# EEZ_DIB_DCM220_r2B4.net
KiCad netlist of a schematic drawn in EAGLE
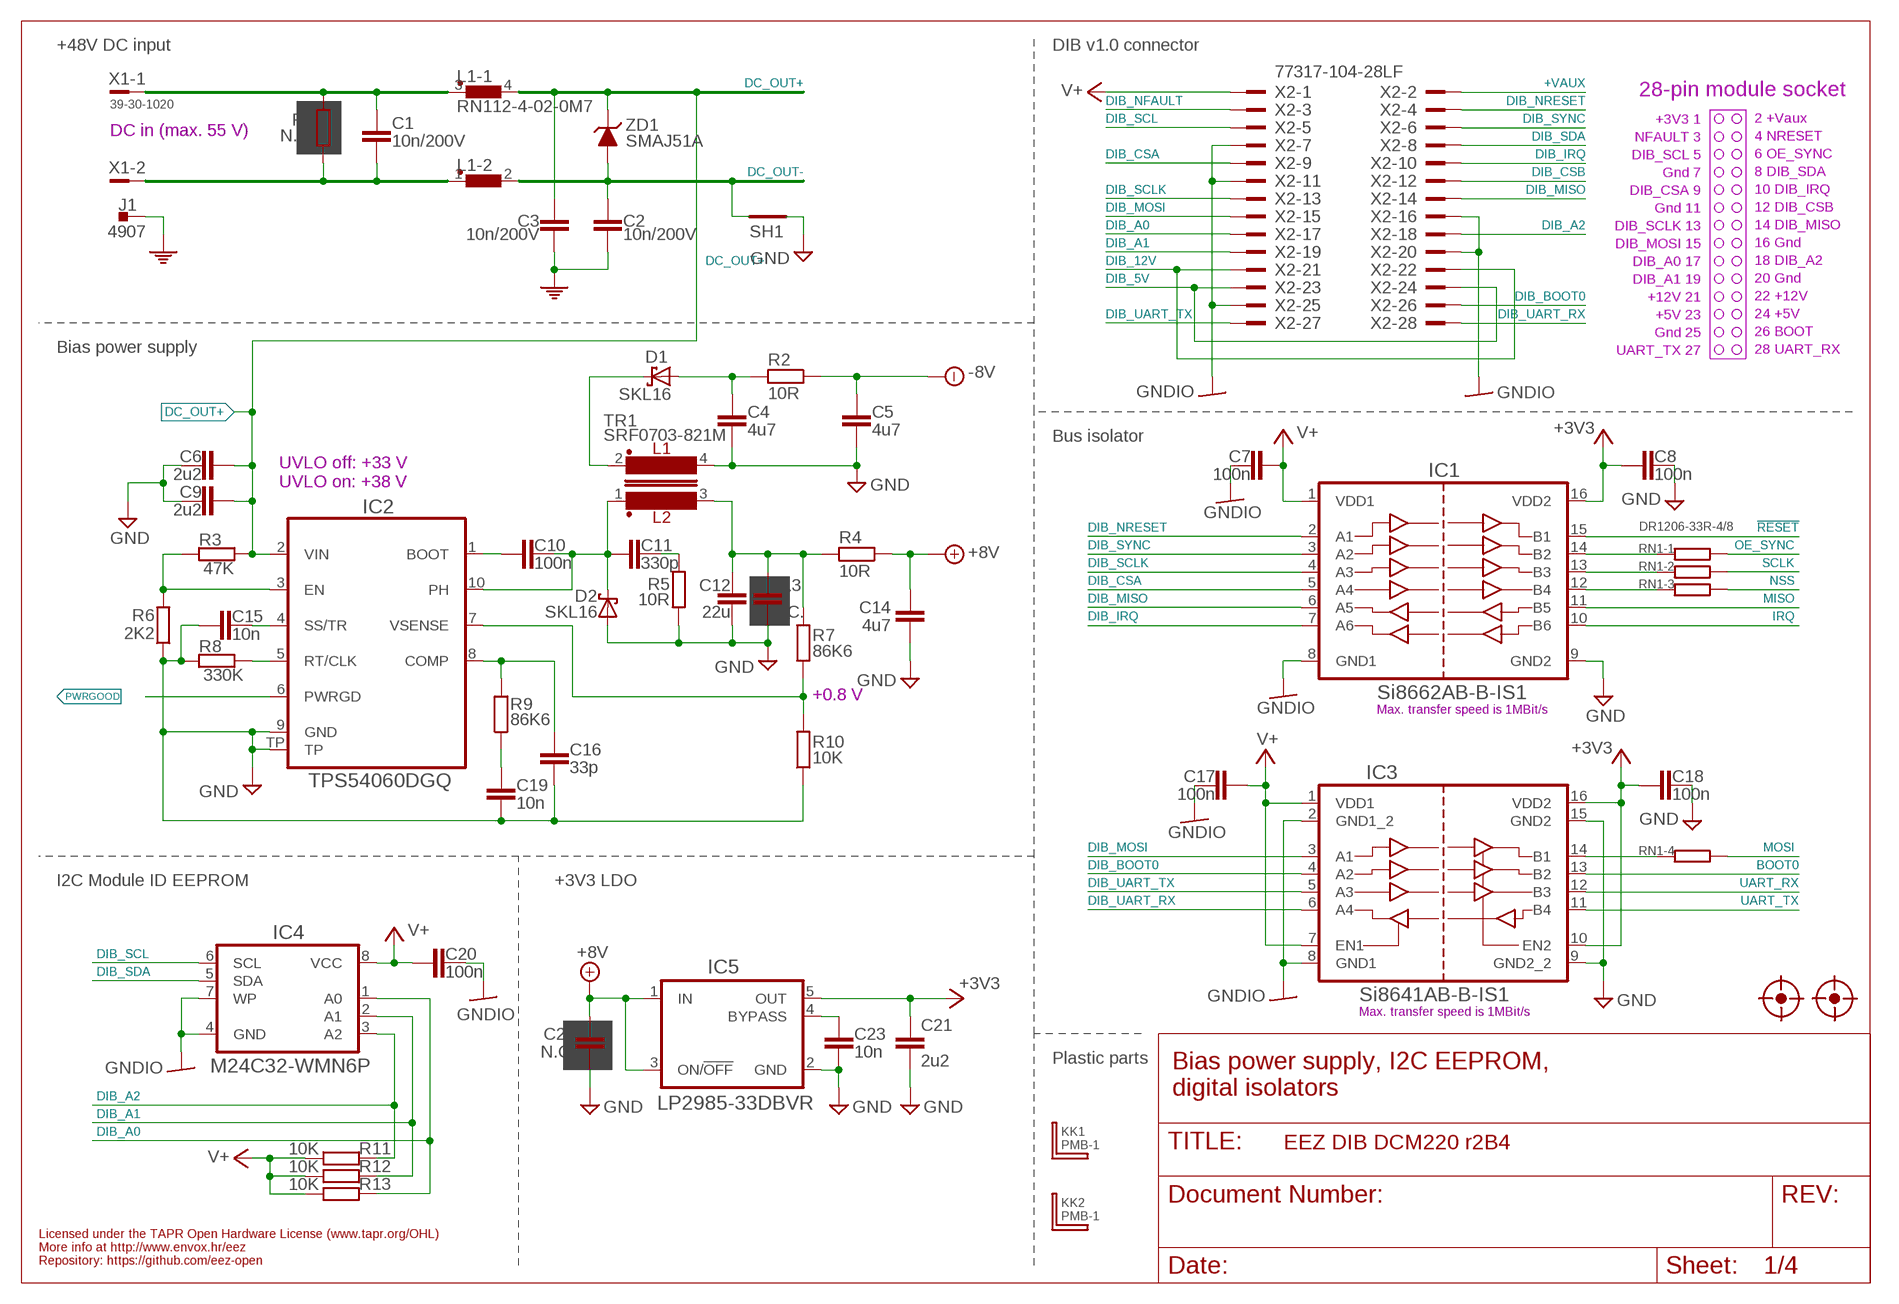
[diagram p0: schematic, sheet 1]
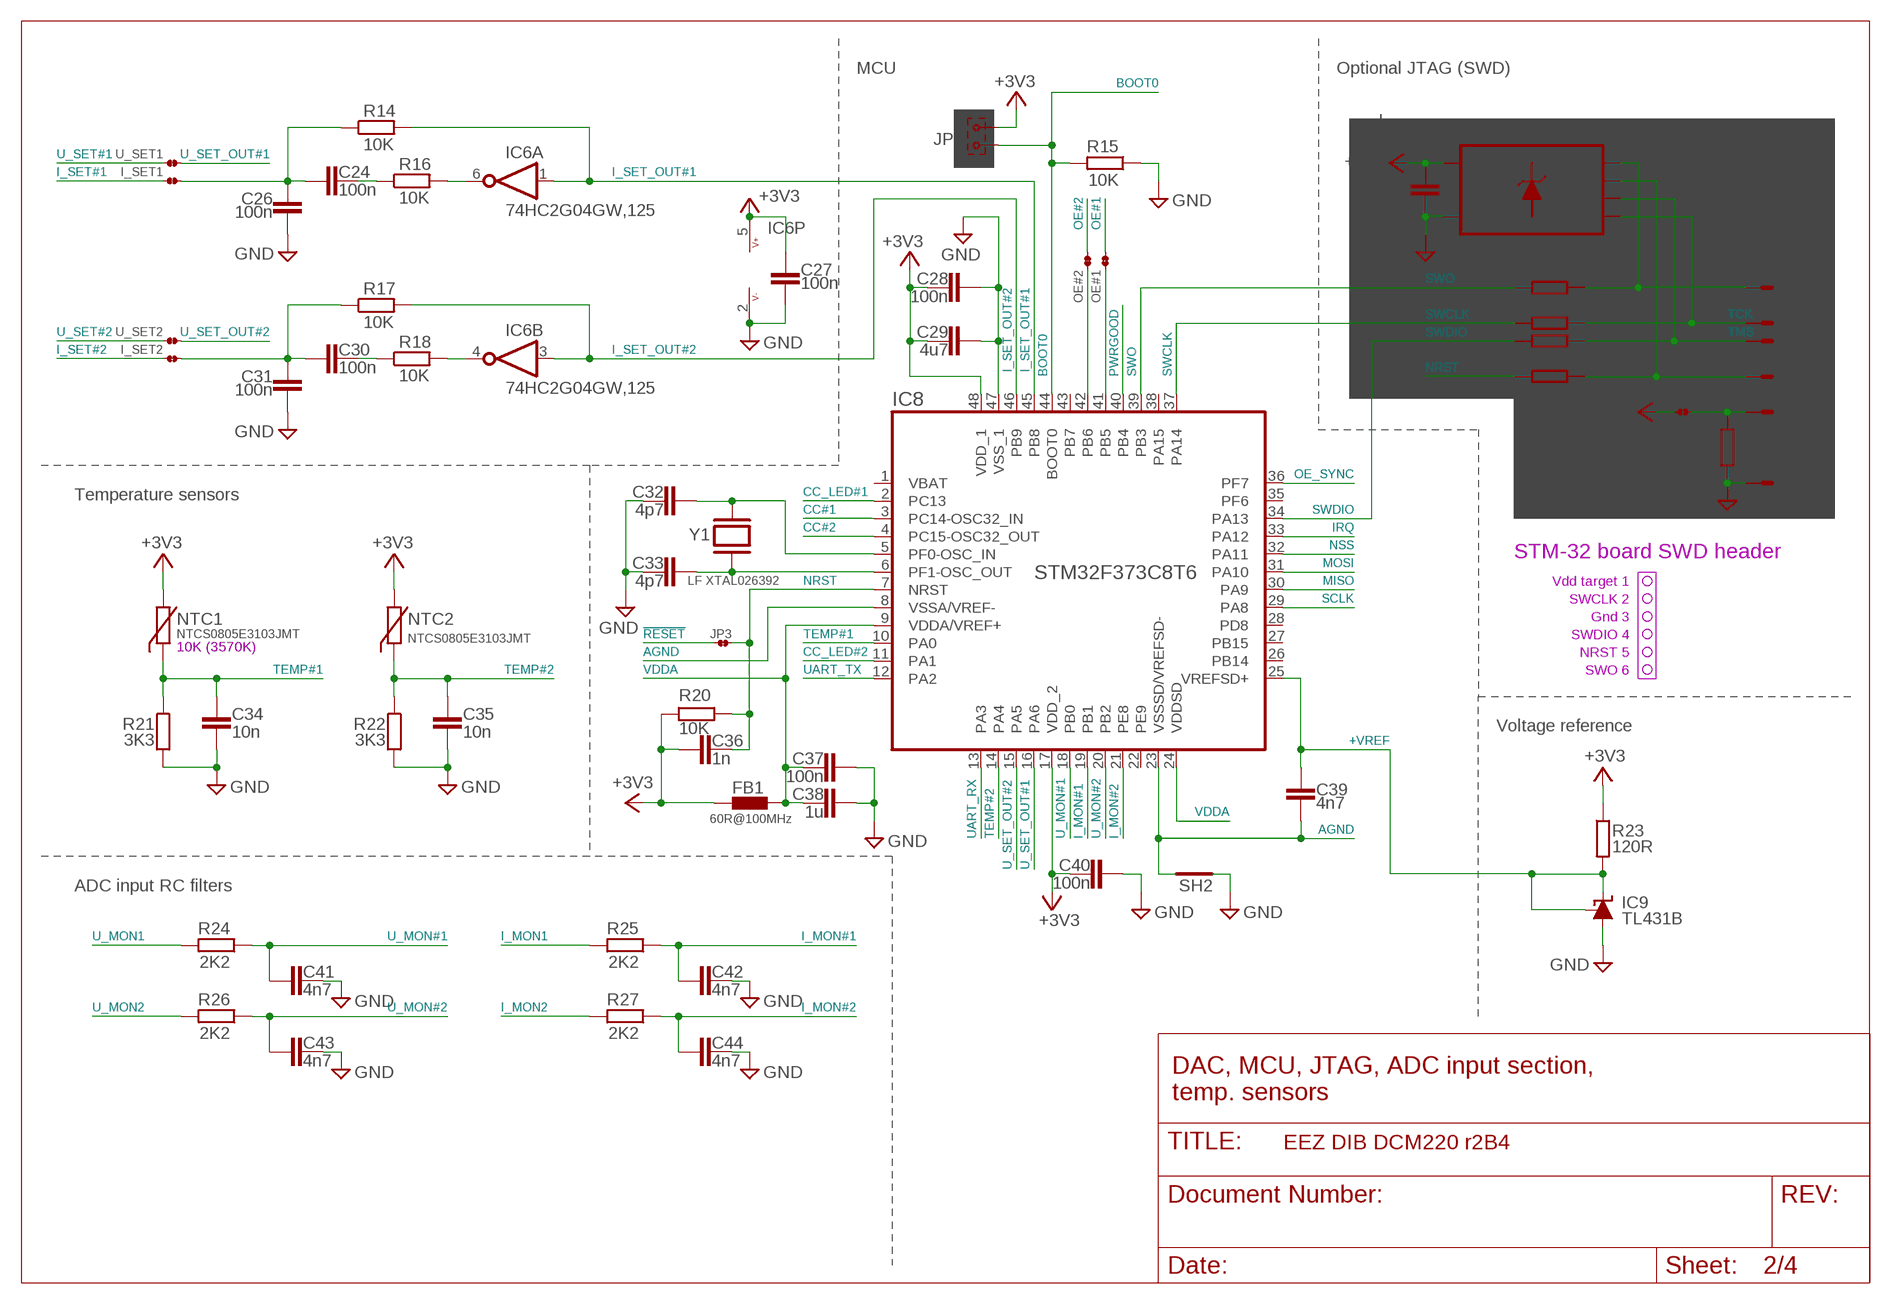
[diagram p1: schematic, sheet 2]
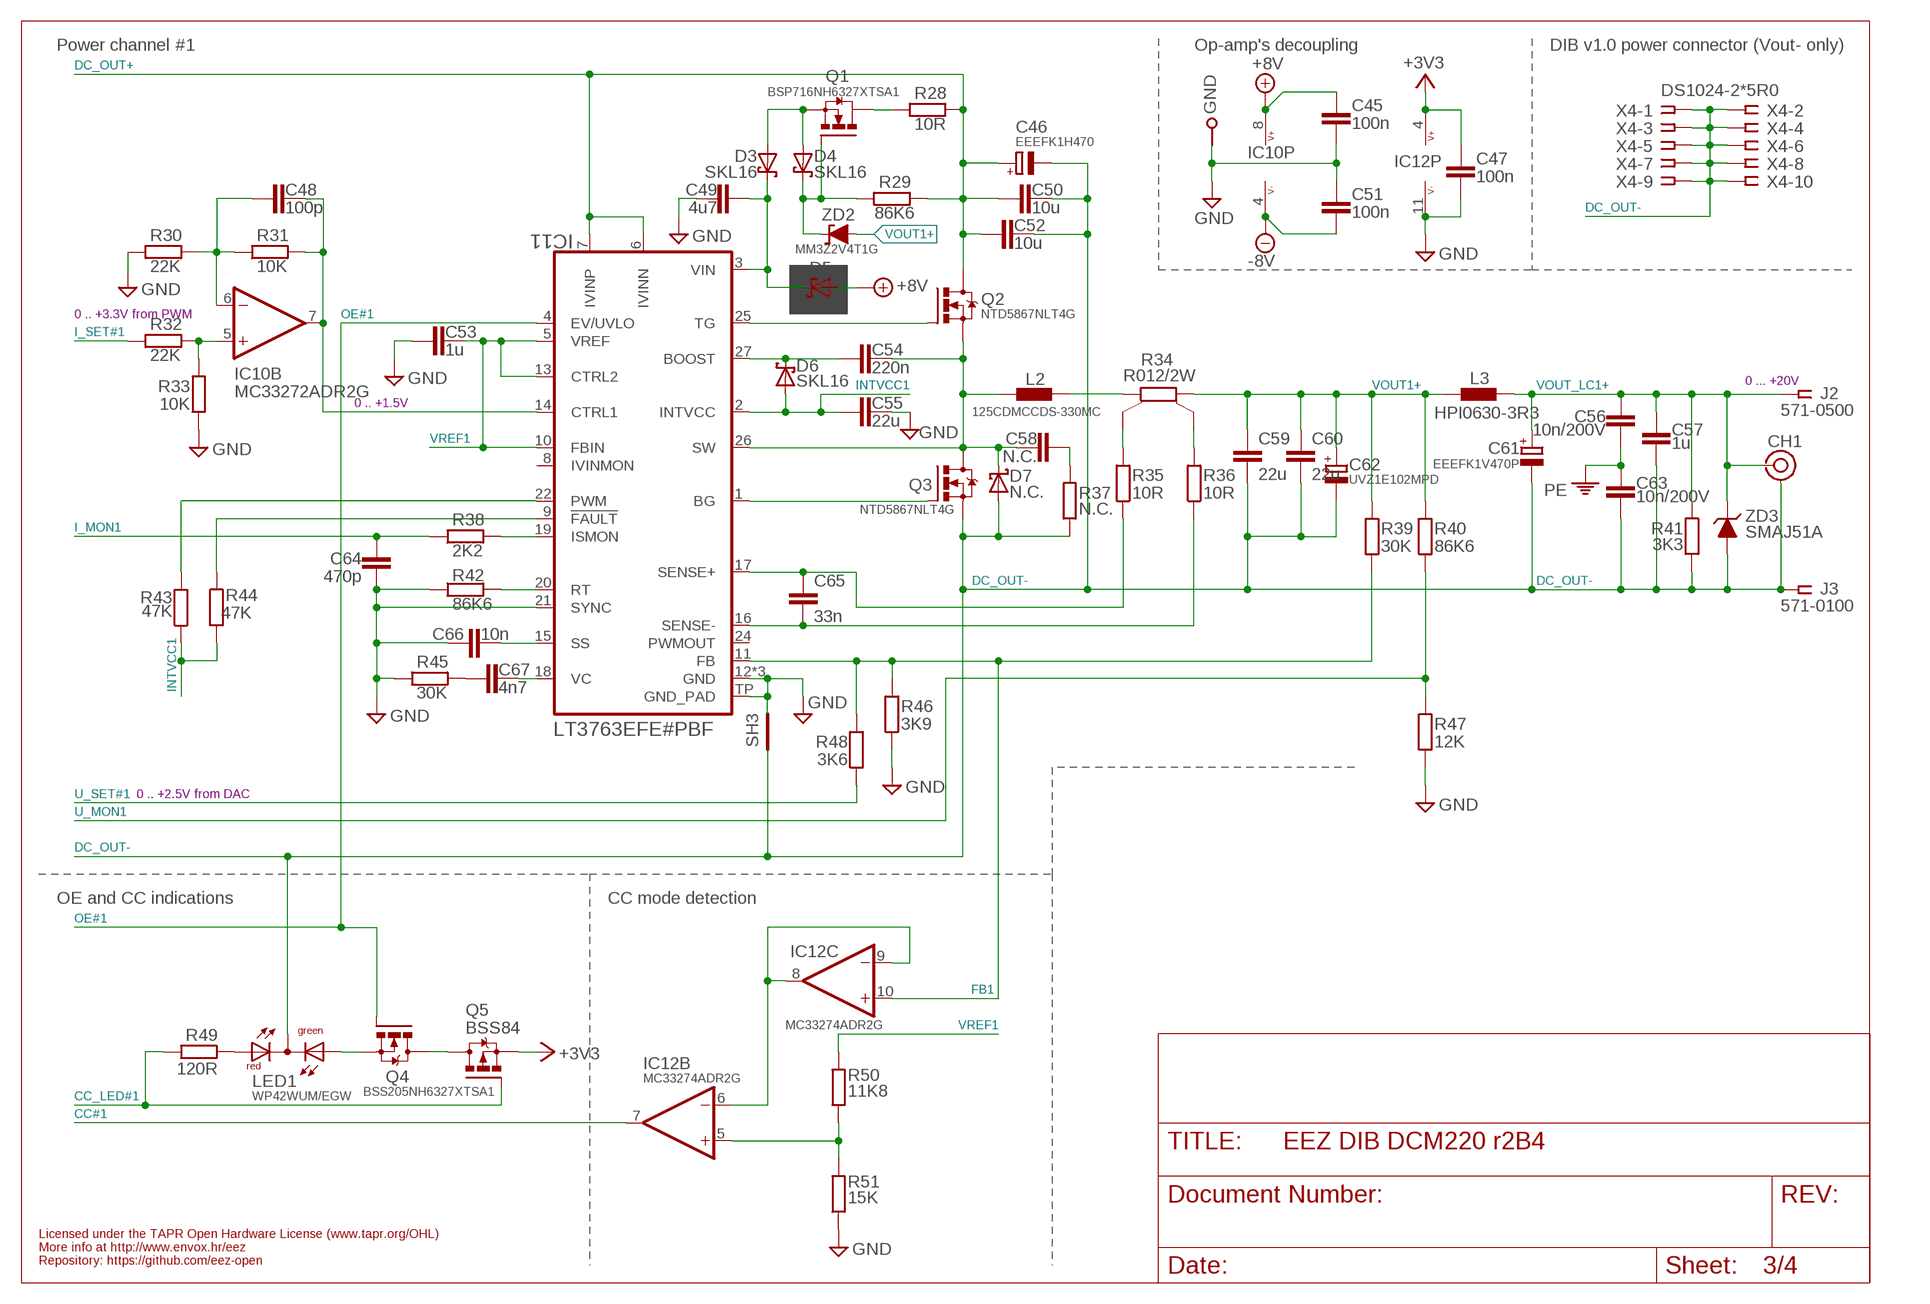
[diagram p2: schematic, sheet 3]
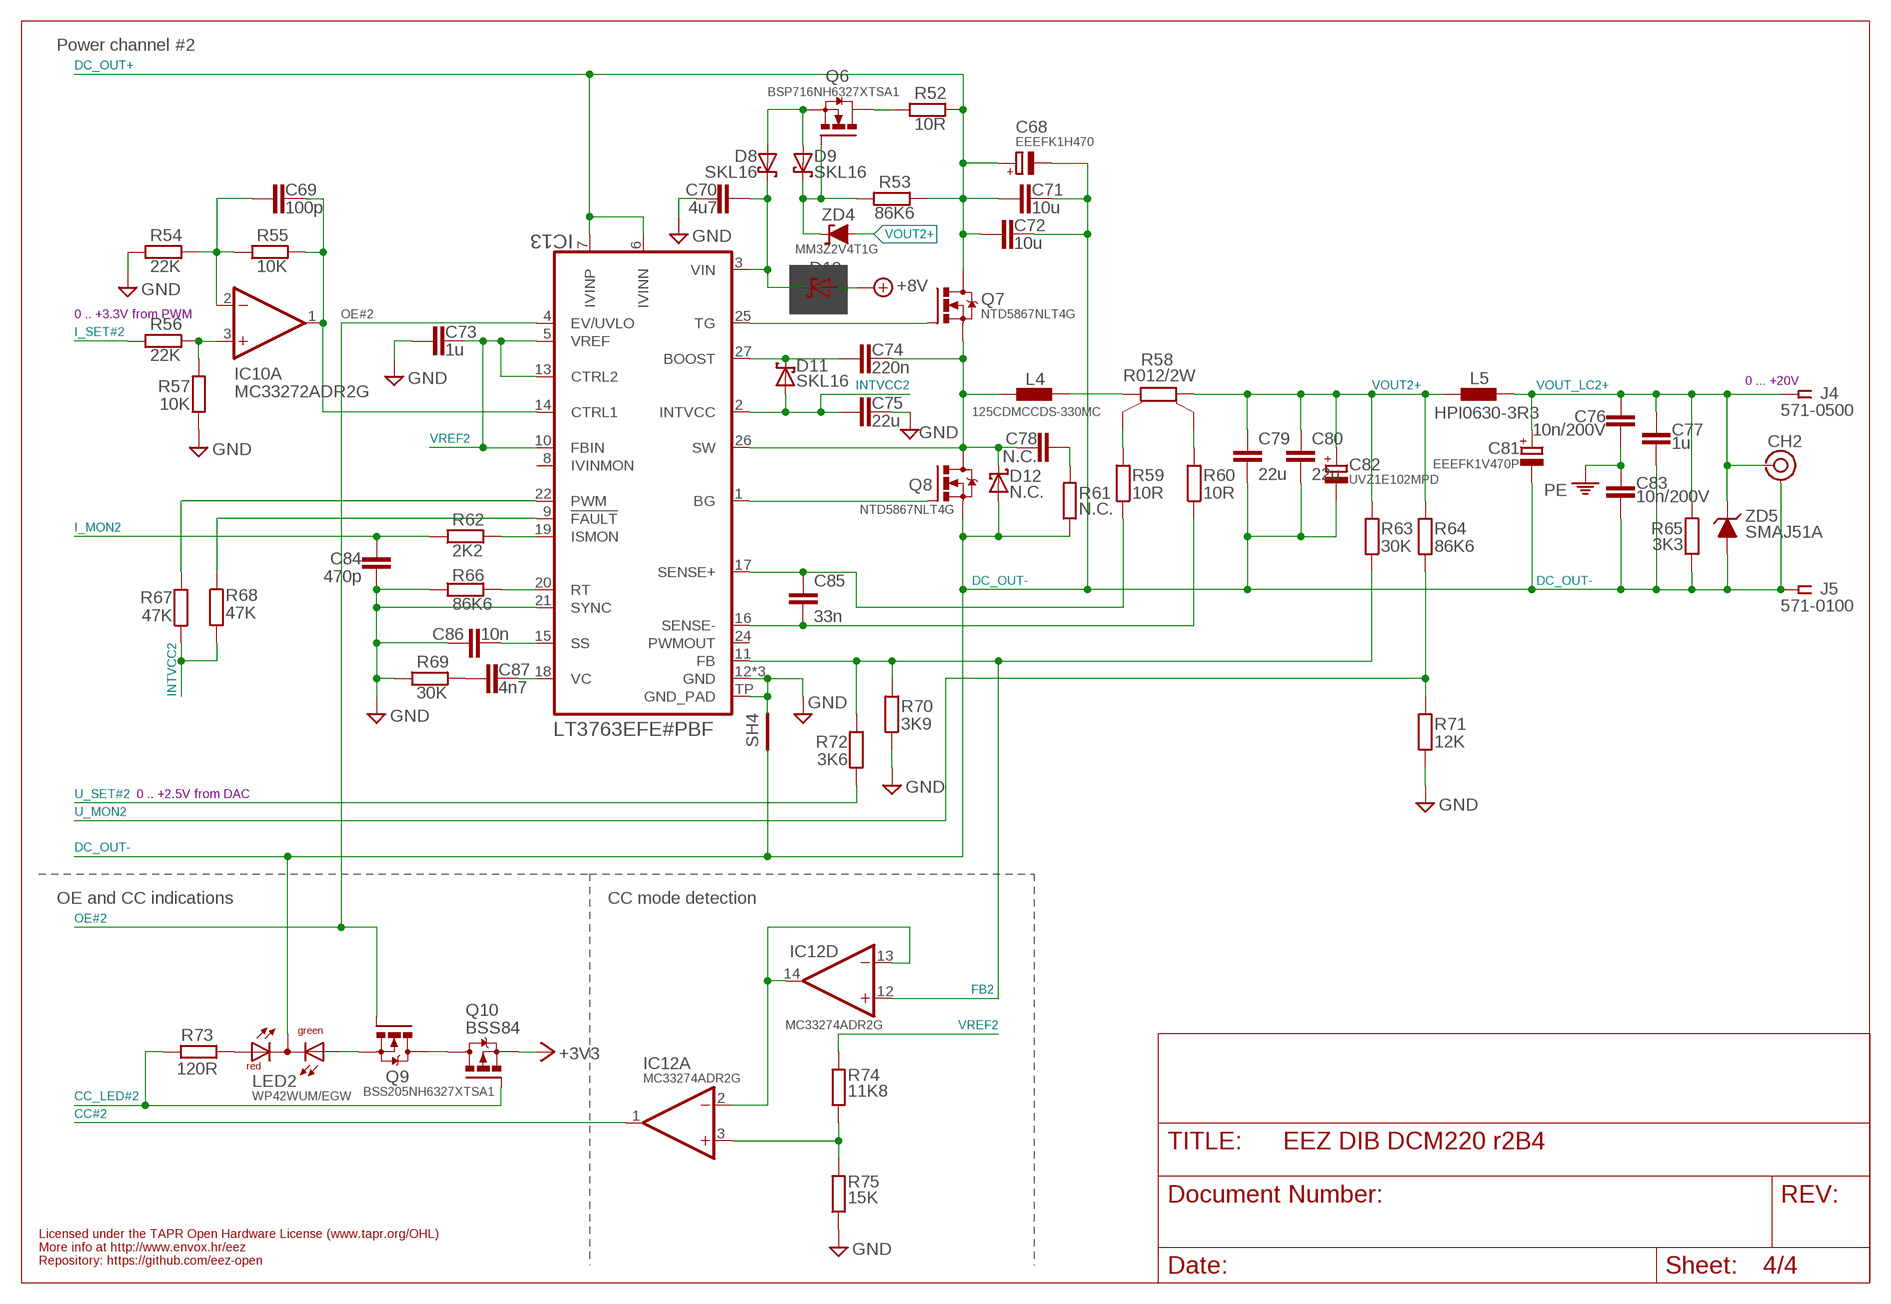
[diagram p3: schematic, sheet 4]

(export (version "E")
  (design (tool "Eeschema 10.0.6"))
  (components
    (comp (ref "C1")
      (value "10n/200V")
      (footprint "eagle-import:C1206")
      (libsource (lib "eagle-import") (part "C-EUC1206"))
    )
    (comp (ref "C2")
      (value "10n/200V")
      (footprint "eagle-import:C1206")
      (libsource (lib "eagle-import") (part "C-EUC1206"))
    )
    (comp (ref "C3")
      (value "10n/200V")
      (footprint "eagle-import:C1206")
      (libsource (lib "eagle-import") (part "C-EUC1206"))
    )
    (comp (ref "C4")
      (value "4u7")
      (footprint "eagle-import:C1206")
      (libsource (lib "eagle-import") (part "C-EUC1206"))
    )
    (comp (ref "C5")
      (value "4u7")
      (footprint "eagle-import:C1206")
      (libsource (lib "eagle-import") (part "C-EUC1206"))
    )
    (comp (ref "C6")
      (value "2u2")
      (footprint "eagle-import:C1206")
      (libsource (lib "eagle-import") (part "C-EUC1206"))
    )
    (comp (ref "C7")
      (value "100n")
      (footprint "eagle-import:C0603")
      (libsource (lib "eagle-import") (part "C-EUC0603"))
    )
    (comp (ref "C8")
      (value "100n")
      (footprint "eagle-import:C0603")
      (libsource (lib "eagle-import") (part "C-EUC0603"))
    )
    (comp (ref "C9")
      (value "2u2")
      (footprint "eagle-import:C1206")
      (libsource (lib "eagle-import") (part "C-EUC1206"))
    )
    (comp (ref "C10")
      (value "100n")
      (footprint "eagle-import:C0603")
      (libsource (lib "eagle-import") (part "C-EUC0603"))
    )
    (comp (ref "C11")
      (value "330p")
      (footprint "eagle-import:C0805")
      (libsource (lib "eagle-import") (part "C-EUC0805"))
    )
    (comp (ref "C12")
      (value "22u")
      (footprint "eagle-import:C1206")
      (libsource (lib "eagle-import") (part "C-EUC1206"))
    )
    (comp (ref "C13")
      (value "N.C.")
      (footprint "eagle-import:C1206")
      (libsource (lib "eagle-import") (part "C-EUC1206"))
    )
    (comp (ref "C14")
      (value "4u7")
      (footprint "eagle-import:C1206")
      (libsource (lib "eagle-import") (part "C-EUC1206"))
    )
    (comp (ref "C15")
      (value "10n")
      (footprint "eagle-import:C0805")
      (libsource (lib "eagle-import") (part "C-EUC0805"))
    )
    (comp (ref "C16")
      (value "33p")
      (footprint "eagle-import:C0603")
      (libsource (lib "eagle-import") (part "C-EUC0603"))
    )
    (comp (ref "C17")
      (value "100n")
      (footprint "eagle-import:C0603")
      (libsource (lib "eagle-import") (part "C-EUC0603"))
    )
    (comp (ref "C18")
      (value "100n")
      (footprint "eagle-import:C0603")
      (libsource (lib "eagle-import") (part "C-EUC0603"))
    )
    (comp (ref "C19")
      (value "10n")
      (footprint "eagle-import:C0805")
      (libsource (lib "eagle-import") (part "C-EUC0805"))
    )
    (comp (ref "C20")
      (value "100n")
      (footprint "eagle-import:C0603")
      (libsource (lib "eagle-import") (part "C-EUC0603"))
    )
    (comp (ref "C21")
      (value "2u2")
      (footprint "eagle-import:C1206")
      (libsource (lib "eagle-import") (part "C-EUC1206"))
    )
    (comp (ref "C22")
      (value "N.C.")
      (footprint "eagle-import:C0805")
      (libsource (lib "eagle-import") (part "C-EUC0805"))
    )
    (comp (ref "C23")
      (value "10n")
      (footprint "eagle-import:C0805")
      (libsource (lib "eagle-import") (part "C-EUC0805"))
    )
    (comp (ref "D1")
      (value "SKL16")
      (footprint "eagle-import:SOD123")
      (libsource (lib "eagle-import") (part "SCHOTTKYSOD123"))
    )
    (comp (ref "D2")
      (value "SKL16")
      (footprint "eagle-import:SOD123")
      (libsource (lib "eagle-import") (part "SCHOTTKYSOD123"))
    )
    (comp (ref "FM1")
      (value "FIDUCIAL_2")
      (footprint "eagle-import:FIDUCIAL_DUAL")
      (libsource (lib "eagle-import") (part "FIDUCIAL_2"))
    )
    (comp (ref "FM2")
      (value "FIDUCIAL_2")
      (footprint "eagle-import:FIDUCIAL_DUAL")
      (libsource (lib "eagle-import") (part "FIDUCIAL_2"))
    )
    (comp (ref "IC1")
      (value "Si8662AB-B-IS1")
      (footprint "eagle-import:SOIC-16")
      (libsource (lib "eagle-import") (part "SI8662NSOIC-16"))
    )
    (comp (ref "IC2")
      (value "TPS54060DGQ")
      (footprint "eagle-import:SOP50P490X110-11N")
      (fields (field (name "MPN") "TPS54060ADGQ"))
      (libsource (lib "eagle-import") (part "TPS54060DGQ"))
    )
    (comp (ref "IC3")
      (value "Si8641AB-B-IS1")
      (footprint "eagle-import:SOIC-16")
      (libsource (lib "eagle-import") (part "SI8641NSOIC-16"))
    )
    (comp (ref "IC4")
      (value "M24C32-WMN6P")
      (footprint "eagle-import:SOIC127P600X173-8N")
      (libsource (lib "eagle-import") (part "AT24CXXSOIC8"))
    )
    (comp (ref "IC5")
      (value "LP2985-33DBVR")
      (footprint "eagle-import:SOT95P270X145-5N")
      (libsource (lib "eagle-import") (part "LP2985"))
    )
    (comp (ref "J1")
      (value "4907")
      (footprint "eagle-import:PCB_TAB-4907")
      (libsource (lib "eagle-import") (part "PCB_TAB-4907"))
    )
    (comp (ref "KK1")
      (value "PMB-1")
      (footprint "eagle-import:PCB-MB")
      (libsource (lib "eagle-import") (part "PCB-MB"))
    )
    (comp (ref "KK2")
      (value "PMB-1")
      (footprint "eagle-import:PCB-MB")
      (libsource (lib "eagle-import") (part "PCB-MB"))
    )
    (comp (ref "L1")
      (value "RN112-4-02-0M7")
      (footprint "eagle-import:RN112")
      (libsource (lib "eagle-import") (part "RN112"))
    )
    (comp (ref "R1")
      (value "N.C.")
      (footprint "eagle-import:R2512")
      (libsource (lib "eagle-import") (part "R-EU_R2512"))
    )
    (comp (ref "R2")
      (value "10R")
      (footprint "eagle-import:R0805")
      (libsource (lib "eagle-import") (part "R-EU_R0805"))
    )
    (comp (ref "R3")
      (value "47K")
      (footprint "eagle-import:R0805")
      (libsource (lib "eagle-import") (part "R-EU_R0805"))
    )
    (comp (ref "R4")
      (value "10R")
      (footprint "eagle-import:R0805")
      (libsource (lib "eagle-import") (part "R-EU_R0805"))
    )
    (comp (ref "R5")
      (value "10R")
      (footprint "eagle-import:R0805")
      (libsource (lib "eagle-import") (part "R-EU_R0805"))
    )
    (comp (ref "R6")
      (value "2K2")
      (footprint "eagle-import:R0805")
      (libsource (lib "eagle-import") (part "R-EU_R0805"))
    )
    (comp (ref "R7")
      (value "86K6")
      (footprint "eagle-import:R0805")
      (libsource (lib "eagle-import") (part "R-EU_R0805"))
    )
    (comp (ref "R8")
      (value "330K")
      (footprint "eagle-import:R0805")
      (libsource (lib "eagle-import") (part "R-EU_R0805"))
    )
    (comp (ref "R9")
      (value "86K6")
      (footprint "eagle-import:R0805")
      (libsource (lib "eagle-import") (part "R-EU_R0805"))
    )
    (comp (ref "R10")
      (value "10K")
      (footprint "eagle-import:R0805")
      (libsource (lib "eagle-import") (part "R-EU_R0805"))
    )
    (comp (ref "R11")
      (value "10K")
      (footprint "eagle-import:R0805")
      (libsource (lib "eagle-import") (part "R-EU_R0805"))
    )
    (comp (ref "R12")
      (value "10K")
      (footprint "eagle-import:R0805")
      (libsource (lib "eagle-import") (part "R-EU_R0805"))
    )
    (comp (ref "R13")
      (value "10K")
      (footprint "eagle-import:R0805")
      (libsource (lib "eagle-import") (part "R-EU_R0805"))
    )
    (comp (ref "RN1")
      (value "DR1206-33R-4/8")
      (footprint "eagle-import:CAY16")
      (libsource (lib "eagle-import") (part "R_ARRAY4"))
    )
    (comp (ref "SH1")
      (value "SHORTNOHOLE")
      (footprint "eagle-import:SHORT_NOHOLE")
      (libsource (lib "eagle-import") (part "SHORTNOHOLE"))
    )
    (comp (ref "TR1")
      (value "SRF0703-821M")
      (footprint "eagle-import:SRF0703")
      (libsource (lib "eagle-import") (part "BOURNS_SRF0703INV"))
    )
    (comp (ref "X1")
      (value "39-30-1020")
      (footprint "eagle-import:MINIFIT_39301020")
      (libsource (lib "eagle-import") (part "MINIFIT_39301020"))
    )
    (comp (ref "X2")
      (value "77317-104-28LF")
      (footprint "eagle-import:77317-104-28LF")
      (libsource (lib "eagle-import") (part "77317-104-28LF"))
    )
    (comp (ref "ZD1")
      (value "SMAJ51A")
      (footprint "eagle-import:DO214AA")
      (libsource (lib "eagle-import") (part "P6SMB68A"))
    )
    (comp (ref "C68")
      (value "EEEFK1H470")
      (footprint "eagle-import:CAPAE830X1050N")
      (libsource (lib "eagle-import") (part "ECAPSMD8.3MM/HA0"))
    )
    (comp (ref "C69")
      (value "100p")
      (footprint "eagle-import:C0805")
      (libsource (lib "eagle-import") (part "C-EUC0805"))
    )
    (comp (ref "C70")
      (value "4u7")
      (footprint "eagle-import:C1206")
      (libsource (lib "eagle-import") (part "C-EUC1206"))
    )
    (comp (ref "C71")
      (value "10u")
      (footprint "eagle-import:C1210")
      (libsource (lib "eagle-import") (part "C-EUC1210"))
    )
    (comp (ref "C72")
      (value "10u")
      (footprint "eagle-import:C1210")
      (libsource (lib "eagle-import") (part "C-EUC1210"))
    )
    (comp (ref "C73")
      (value "1u")
      (footprint "eagle-import:C0805")
      (libsource (lib "eagle-import") (part "C-EUC0805"))
    )
    (comp (ref "C74")
      (value "220n")
      (footprint "eagle-import:C0805")
      (libsource (lib "eagle-import") (part "C-EUC0805"))
    )
    (comp (ref "C75")
      (value "22u")
      (footprint "eagle-import:C1206")
      (libsource (lib "eagle-import") (part "C-EUC1206"))
    )
    (comp (ref "C76")
      (value "10n/200V")
      (footprint "eagle-import:C1206")
      (libsource (lib "eagle-import") (part "C-EUC1206"))
    )
    (comp (ref "C77")
      (value "1u")
      (footprint "eagle-import:C0805")
      (libsource (lib "eagle-import") (part "C-EUC0805"))
    )
    (comp (ref "C78")
      (value "N.C.")
      (footprint "eagle-import:C0805")
      (libsource (lib "eagle-import") (part "C-EUC0805"))
    )
    (comp (ref "C79")
      (value "22u")
      (footprint "eagle-import:C1210")
      (libsource (lib "eagle-import") (part "C-EUC1210"))
    )
    (comp (ref "C80")
      (value "22u")
      (footprint "eagle-import:C1210")
      (libsource (lib "eagle-import") (part "C-EUC1210"))
    )
    (comp (ref "C81")
      (value "EEEFK1V470P")
      (footprint "eagle-import:CAPAE660X610N")
      (libsource (lib "eagle-import") (part "ECAPPANASONIC_H"))
    )
    (comp (ref "C82")
      (value "UVZ1E102MPD")
      (footprint "eagle-import:ECAP5_10.5")
      (libsource (lib "eagle-import") (part "ECAP5G_10.5MM"))
    )
    (comp (ref "C83")
      (value "10n/200V")
      (footprint "eagle-import:C1206")
      (libsource (lib "eagle-import") (part "C-EUC1206"))
    )
    (comp (ref "C84")
      (value "470p")
      (footprint "eagle-import:C0805")
      (libsource (lib "eagle-import") (part "C-EUC0805"))
    )
    (comp (ref "C85")
      (value "33n")
      (footprint "eagle-import:C0805")
      (libsource (lib "eagle-import") (part "C-EUC0805"))
    )
    (comp (ref "C86")
      (value "10n")
      (footprint "eagle-import:C0805")
      (libsource (lib "eagle-import") (part "C-EUC0805"))
    )
    (comp (ref "C87")
      (value "4n7")
      (footprint "eagle-import:C0805")
      (libsource (lib "eagle-import") (part "C-EUC0805"))
    )
    (comp (ref "CH2")
      (value "TEST_POINT-2")
      (footprint "eagle-import:TP_1.1MM_2")
      (libsource (lib "eagle-import") (part "TEST_POINT-2"))
    )
    (comp (ref "D8")
      (value "SKL16")
      (footprint "eagle-import:SOD123")
      (libsource (lib "eagle-import") (part "SCHOTTKYSOD123"))
    )
    (comp (ref "D9")
      (value "SKL16")
      (footprint "eagle-import:SOD123")
      (libsource (lib "eagle-import") (part "SCHOTTKYSOD123"))
    )
    (comp (ref "D10")
      (value "N.C.")
      (footprint "eagle-import:SOD123")
      (libsource (lib "eagle-import") (part "SCHOTTKYSOD123"))
    )
    (comp (ref "D11")
      (value "SKL16")
      (footprint "eagle-import:SOD123")
      (libsource (lib "eagle-import") (part "SCHOTTKYSOD123"))
    )
    (comp (ref "D12")
      (value "N.C.")
      (footprint "eagle-import:SMA")
      (libsource (lib "eagle-import") (part "SCHOTTKYSMA_DO-214AC"))
    )
    (comp (ref "IC10")
      (value "MC33272ADR2G")
      (footprint "eagle-import:SOIC127P600X173-8N")
      (libsource (lib "eagle-import") (part "TL072SOIC8"))
    )
    (comp (ref "IC12")
      (value "MC33274ADR2G")
      (footprint "eagle-import:SOIC127P600X175-14N")
      (fields (field (name "MPN") "TL074ACD"))
      (libsource (lib "eagle-import") (part "TL074SOIC14"))
    )
    (comp (ref "IC13")
      (value "LT3763EFE#PBF")
      (footprint "eagle-import:LTC_05-08-1663-EB")
      (libsource (lib "eagle-import") (part "LT3763EFE#PBF"))
    )
    (comp (ref "J4")
      (value "571-0500")
      (footprint "eagle-import:DELTRON_571")
      (libsource (lib "eagle-import") (part "571-0500"))
    )
    (comp (ref "J5")
      (value "571-0100")
      (footprint "eagle-import:DELTRON_571")
      (libsource (lib "eagle-import") (part "571-0100"))
    )
    (comp (ref "L4")
      (value "125CDMCCDS-330MC")
      (footprint "eagle-import:125CDMCC_DS")
      (libsource (lib "eagle-import") (part "125CDMCC/DS"))
    )
    (comp (ref "L5")
      (value "HPI0630-3R3")
      (footprint "eagle-import:COILCRAFT_HPI0630")
      (libsource (lib "eagle-import") (part "COILCRAFT_HPI0630"))
    )
    (comp (ref "LED2")
      (value "WP42WUM/EGW")
      (footprint "eagle-import:L-42WUM-1EGWT")
      (libsource (lib "eagle-import") (part "LED_L-42WUM/1EGWT"))
    )
    (comp (ref "Q6")
      (value "BSP716NH6327XTSA1")
      (footprint "eagle-import:SOT223")
      (libsource (lib "eagle-import") (part "N-HEXFET-2D_?-SOT232IRLL014N"))
    )
    (comp (ref "Q7")
      (value "NTD5867NLT4G")
      (footprint "eagle-import:TO229P990X239-3N")
      (libsource (lib "eagle-import") (part "N-MOSFETDPAK"))
    )
    (comp (ref "Q8")
      (value "NTD5867NLT4G")
      (footprint "eagle-import:TO229P990X239-3N")
      (libsource (lib "eagle-import") (part "N-MOSFETDPAK"))
    )
    (comp (ref "Q9")
      (value "BSS205NH6327XTSA1")
      (footprint "eagle-import:SOT103P240X110-3N")
      (fields (field (name "MPN") "2N7002-7-F"))
      (libsource (lib "eagle-import") (part "2N7002"))
    )
    (comp (ref "Q10")
      (value "BSS84")
      (footprint "eagle-import:SOT95P237X112-3N")
      (fields (field (name "MPN") "IRLML2246TRPBF"))
      (libsource (lib "eagle-import") (part "IRLML2246TRPBF"))
    )
    (comp (ref "R52")
      (value "10R")
      (footprint "eagle-import:R0805")
      (libsource (lib "eagle-import") (part "R-EU_R0805"))
    )
    (comp (ref "R53")
      (value "86K6")
      (footprint "eagle-import:R0805")
      (libsource (lib "eagle-import") (part "R-EU_R0805"))
    )
    (comp (ref "R54")
      (value "22K")
      (footprint "eagle-import:R0805")
      (libsource (lib "eagle-import") (part "R-EU_R0805"))
    )
    (comp (ref "R55")
      (value "10K")
      (footprint "eagle-import:R0805")
      (libsource (lib "eagle-import") (part "R-EU_R0805"))
    )
    (comp (ref "R56")
      (value "22K")
      (footprint "eagle-import:R0805")
      (libsource (lib "eagle-import") (part "R-EU_R0805"))
    )
    (comp (ref "R57")
      (value "10K")
      (footprint "eagle-import:R0805")
      (libsource (lib "eagle-import") (part "R-EU_R0805"))
    )
    (comp (ref "R58")
      (value "R012/2W")
      (footprint "eagle-import:R_2512-4WIRE")
      (libsource (lib "eagle-import") (part "R-EU_4WIRE2512"))
    )
    (comp (ref "R59")
      (value "10R")
      (footprint "eagle-import:R0805")
      (libsource (lib "eagle-import") (part "R-EU_R0805"))
    )
    (comp (ref "R60")
      (value "10R")
      (footprint "eagle-import:R0805")
      (libsource (lib "eagle-import") (part "R-EU_R0805"))
    )
    (comp (ref "R61")
      (value "N.C.")
      (footprint "eagle-import:R1206")
      (libsource (lib "eagle-import") (part "R-EU_R1206"))
    )
    (comp (ref "R62")
      (value "2K2")
      (footprint "eagle-import:R0805")
      (libsource (lib "eagle-import") (part "R-EU_R0805"))
    )
    (comp (ref "R63")
      (value "30K")
      (footprint "eagle-import:R0805")
      (libsource (lib "eagle-import") (part "R-EU_R0805"))
    )
    (comp (ref "R64")
      (value "86K6")
      (footprint "eagle-import:R0805")
      (libsource (lib "eagle-import") (part "R-EU_R0805"))
    )
    (comp (ref "R65")
      (value "3K3")
      (footprint "eagle-import:R0805")
      (libsource (lib "eagle-import") (part "R-EU_R0805"))
    )
    (comp (ref "R66")
      (value "86K6")
      (footprint "eagle-import:R0805")
      (libsource (lib "eagle-import") (part "R-EU_R0805"))
    )
    (comp (ref "R67")
      (value "47K")
      (footprint "eagle-import:R0805")
      (libsource (lib "eagle-import") (part "R-EU_R0805"))
    )
    (comp (ref "R68")
      (value "47K")
      (footprint "eagle-import:R0805")
      (libsource (lib "eagle-import") (part "R-EU_R0805"))
    )
    (comp (ref "R69")
      (value "30K")
      (footprint "eagle-import:R0805")
      (libsource (lib "eagle-import") (part "R-EU_R0805"))
    )
    (comp (ref "R70")
      (value "3K9")
      (footprint "eagle-import:R0805")
      (libsource (lib "eagle-import") (part "R-EU_R0805"))
    )
    (comp (ref "R71")
      (value "12K")
      (footprint "eagle-import:R0805")
      (libsource (lib "eagle-import") (part "R-EU_R0805"))
    )
    (comp (ref "R72")
      (value "3K6")
      (footprint "eagle-import:R0805")
      (libsource (lib "eagle-import") (part "R-EU_R0805"))
    )
    (comp (ref "R73")
      (value "120R")
      (footprint "eagle-import:R0805")
      (libsource (lib "eagle-import") (part "R-EU_R0805"))
    )
    (comp (ref "R74")
      (value "11K8")
      (footprint "eagle-import:R0805")
      (libsource (lib "eagle-import") (part "R-EU_R0805"))
    )
    (comp (ref "R75")
      (value "15K")
      (footprint "eagle-import:R0805")
      (libsource (lib "eagle-import") (part "R-EU_R0805"))
    )
    (comp (ref "SH4")
      (value "SHORTNOHOLE")
      (footprint "eagle-import:SHORT_NOHOLE")
      (libsource (lib "eagle-import") (part "SHORTNOHOLE"))
    )
    (comp (ref "ZD4")
      (value "MM3Z2V4T1G")
      (footprint "eagle-import:SOD323-W")
      (libsource (lib "eagle-import") (part "ZENER-DIODESOD323"))
    )
    (comp (ref "ZD5")
      (value "SMAJ51A")
      (footprint "eagle-import:DO214AA")
      (libsource (lib "eagle-import") (part "P6SMB68A"))
    )
    (comp (ref "C45")
      (value "100n")
      (footprint "eagle-import:C0603")
      (libsource (lib "eagle-import") (part "C-EUC0603"))
    )
    (comp (ref "C46")
      (value "EEEFK1H470")
      (footprint "eagle-import:CAPAE830X1050N")
      (libsource (lib "eagle-import") (part "ECAPSMD8.3MM/HA0"))
    )
    (comp (ref "C47")
      (value "100n")
      (footprint "eagle-import:C0603")
      (libsource (lib "eagle-import") (part "C-EUC0603"))
    )
    (comp (ref "C48")
      (value "100p")
      (footprint "eagle-import:C0805")
      (libsource (lib "eagle-import") (part "C-EUC0805"))
    )
    (comp (ref "C49")
      (value "4u7")
      (footprint "eagle-import:C1206")
      (libsource (lib "eagle-import") (part "C-EUC1206"))
    )
    (comp (ref "C50")
      (value "10u")
      (footprint "eagle-import:C1210")
      (libsource (lib "eagle-import") (part "C-EUC1210"))
    )
    (comp (ref "C51")
      (value "100n")
      (footprint "eagle-import:C0603")
      (libsource (lib "eagle-import") (part "C-EUC0603"))
    )
    (comp (ref "C52")
      (value "10u")
      (footprint "eagle-import:C1210")
      (libsource (lib "eagle-import") (part "C-EUC1210"))
    )
    (comp (ref "C53")
      (value "1u")
      (footprint "eagle-import:C0805")
      (libsource (lib "eagle-import") (part "C-EUC0805"))
    )
    (comp (ref "C54")
      (value "220n")
      (footprint "eagle-import:C0805")
      (libsource (lib "eagle-import") (part "C-EUC0805"))
    )
    (comp (ref "C55")
      (value "22u")
      (footprint "eagle-import:C1206")
      (libsource (lib "eagle-import") (part "C-EUC1206"))
    )
    (comp (ref "C56")
      (value "10n/200V")
      (footprint "eagle-import:C1206")
      (libsource (lib "eagle-import") (part "C-EUC1206"))
    )
    (comp (ref "C57")
      (value "1u")
      (footprint "eagle-import:C0805")
      (libsource (lib "eagle-import") (part "C-EUC0805"))
    )
    (comp (ref "C58")
      (value "N.C.")
      (footprint "eagle-import:C0805")
      (libsource (lib "eagle-import") (part "C-EUC0805"))
    )
    (comp (ref "C59")
      (value "22u")
      (footprint "eagle-import:C1210")
      (libsource (lib "eagle-import") (part "C-EUC1210"))
    )
    (comp (ref "C60")
      (value "22u")
      (footprint "eagle-import:C1210")
      (libsource (lib "eagle-import") (part "C-EUC1210"))
    )
    (comp (ref "C61")
      (value "EEEFK1V470P")
      (footprint "eagle-import:CAPAE660X610N")
      (libsource (lib "eagle-import") (part "ECAPPANASONIC_H"))
    )
    (comp (ref "C62")
      (value "UVZ1E102MPD")
      (footprint "eagle-import:ECAP5_10.5")
      (libsource (lib "eagle-import") (part "ECAP5G_10.5MM"))
    )
    (comp (ref "C63")
      (value "10n/200V")
      (footprint "eagle-import:C1206")
      (libsource (lib "eagle-import") (part "C-EUC1206"))
    )
    (comp (ref "C64")
      (value "470p")
      (footprint "eagle-import:C0805")
      (libsource (lib "eagle-import") (part "C-EUC0805"))
    )
    (comp (ref "C65")
      (value "33n")
      (footprint "eagle-import:C0805")
      (libsource (lib "eagle-import") (part "C-EUC0805"))
    )
    (comp (ref "C66")
      (value "10n")
      (footprint "eagle-import:C0805")
      (libsource (lib "eagle-import") (part "C-EUC0805"))
    )
    (comp (ref "C67")
      (value "4n7")
      (footprint "eagle-import:C0805")
      (libsource (lib "eagle-import") (part "C-EUC0805"))
    )
    (comp (ref "CH1")
      (value "TEST_POINT-2")
      (footprint "eagle-import:TP_1.1MM_2")
      (libsource (lib "eagle-import") (part "TEST_POINT-2"))
    )
    (comp (ref "D3")
      (value "SKL16")
      (footprint "eagle-import:SOD123")
      (libsource (lib "eagle-import") (part "SCHOTTKYSOD123"))
    )
    (comp (ref "D4")
      (value "SKL16")
      (footprint "eagle-import:SOD123")
      (libsource (lib "eagle-import") (part "SCHOTTKYSOD123"))
    )
    (comp (ref "D5")
      (value "N.C.")
      (footprint "eagle-import:SOD123")
      (libsource (lib "eagle-import") (part "SCHOTTKYSOD123"))
    )
    (comp (ref "D6")
      (value "SKL16")
      (footprint "eagle-import:SOD123")
      (libsource (lib "eagle-import") (part "SCHOTTKYSOD123"))
    )
    (comp (ref "D7")
      (value "N.C.")
      (footprint "eagle-import:SMA")
      (libsource (lib "eagle-import") (part "SCHOTTKYSMA_DO-214AC"))
    )
    (comp (ref "GND")
      (value "TEST-PIN_0.9MM")
      (footprint "eagle-import:TEST-PIN_0.9MM")
      (libsource (lib "eagle-import") (part "TEST-PIN_0.9MM"))
    )
    (comp (ref "IC11")
      (value "LT3763EFE#PBF")
      (footprint "eagle-import:LTC_05-08-1663-EB")
      (libsource (lib "eagle-import") (part "LT3763EFE#PBF"))
    )
    (comp (ref "J2")
      (value "571-0500")
      (footprint "eagle-import:DELTRON_571")
      (libsource (lib "eagle-import") (part "571-0500"))
    )
    (comp (ref "J3")
      (value "571-0100")
      (footprint "eagle-import:DELTRON_571")
      (libsource (lib "eagle-import") (part "571-0100"))
    )
    (comp (ref "L2")
      (value "125CDMCCDS-330MC")
      (footprint "eagle-import:125CDMCC_DS")
      (libsource (lib "eagle-import") (part "125CDMCC/DS"))
    )
    (comp (ref "L3")
      (value "HPI0630-3R3")
      (footprint "eagle-import:COILCRAFT_HPI0630")
      (libsource (lib "eagle-import") (part "COILCRAFT_HPI0630"))
    )
    (comp (ref "LED1")
      (value "WP42WUM/EGW")
      (footprint "eagle-import:L-42WUM-1EGWT")
      (libsource (lib "eagle-import") (part "LED_L-42WUM/1EGWT"))
    )
    (comp (ref "Q1")
      (value "BSP716NH6327XTSA1")
      (footprint "eagle-import:SOT223")
      (libsource (lib "eagle-import") (part "N-HEXFET-2D_?-SOT232IRLL014N"))
    )
    (comp (ref "Q2")
      (value "NTD5867NLT4G")
      (footprint "eagle-import:TO229P990X239-3N")
      (libsource (lib "eagle-import") (part "N-MOSFETDPAK"))
    )
    (comp (ref "Q3")
      (value "NTD5867NLT4G")
      (footprint "eagle-import:TO229P990X239-3N")
      (libsource (lib "eagle-import") (part "N-MOSFETDPAK"))
    )
    (comp (ref "Q4")
      (value "BSS205NH6327XTSA1")
      (footprint "eagle-import:SOT103P240X110-3N")
      (fields (field (name "MPN") "2N7002-7-F"))
      (libsource (lib "eagle-import") (part "2N7002"))
    )
    (comp (ref "Q5")
      (value "BSS84")
      (footprint "eagle-import:SOT95P237X112-3N")
      (fields (field (name "MPN") "IRLML2246TRPBF"))
      (libsource (lib "eagle-import") (part "IRLML2246TRPBF"))
    )
    (comp (ref "R28")
      (value "10R")
      (footprint "eagle-import:R0805")
      (libsource (lib "eagle-import") (part "R-EU_R0805"))
    )
    (comp (ref "R29")
      (value "86K6")
      (footprint "eagle-import:R0805")
      (libsource (lib "eagle-import") (part "R-EU_R0805"))
    )
    (comp (ref "R30")
      (value "22K")
      (footprint "eagle-import:R0805")
      (libsource (lib "eagle-import") (part "R-EU_R0805"))
    )
    (comp (ref "R31")
      (value "10K")
      (footprint "eagle-import:R0805")
      (libsource (lib "eagle-import") (part "R-EU_R0805"))
    )
    (comp (ref "R32")
      (value "22K")
      (footprint "eagle-import:R0805")
      (libsource (lib "eagle-import") (part "R-EU_R0805"))
    )
    (comp (ref "R33")
      (value "10K")
      (footprint "eagle-import:R0805")
      (libsource (lib "eagle-import") (part "R-EU_R0805"))
    )
    (comp (ref "R34")
      (value "R012/2W")
      (footprint "eagle-import:R_2512-4WIRE")
      (libsource (lib "eagle-import") (part "R-EU_4WIRE2512"))
    )
    (comp (ref "R35")
      (value "10R")
      (footprint "eagle-import:R0805")
      (libsource (lib "eagle-import") (part "R-EU_R0805"))
    )
    (comp (ref "R36")
      (value "10R")
      (footprint "eagle-import:R0805")
      (libsource (lib "eagle-import") (part "R-EU_R0805"))
    )
    (comp (ref "R37")
      (value "N.C.")
      (footprint "eagle-import:R1206")
      (libsource (lib "eagle-import") (part "R-EU_R1206"))
    )
    (comp (ref "R38")
      (value "2K2")
      (footprint "eagle-import:R0805")
      (libsource (lib "eagle-import") (part "R-EU_R0805"))
    )
    (comp (ref "R39")
      (value "30K")
      (footprint "eagle-import:R0805")
      (libsource (lib "eagle-import") (part "R-EU_R0805"))
    )
    (comp (ref "R40")
      (value "86K6")
      (footprint "eagle-import:R0805")
      (libsource (lib "eagle-import") (part "R-EU_R0805"))
    )
    (comp (ref "R41")
      (value "3K3")
      (footprint "eagle-import:R0805")
      (libsource (lib "eagle-import") (part "R-EU_R0805"))
    )
    (comp (ref "R42")
      (value "86K6")
      (footprint "eagle-import:R0805")
      (libsource (lib "eagle-import") (part "R-EU_R0805"))
    )
    (comp (ref "R43")
      (value "47K")
      (footprint "eagle-import:R0805")
      (libsource (lib "eagle-import") (part "R-EU_R0805"))
    )
    (comp (ref "R44")
      (value "47K")
      (footprint "eagle-import:R0805")
      (libsource (lib "eagle-import") (part "R-EU_R0805"))
    )
    (comp (ref "R45")
      (value "30K")
      (footprint "eagle-import:R0805")
      (libsource (lib "eagle-import") (part "R-EU_R0805"))
    )
    (comp (ref "R46")
      (value "3K9")
      (footprint "eagle-import:R0805")
      (libsource (lib "eagle-import") (part "R-EU_R0805"))
    )
    (comp (ref "R47")
      (value "12K")
      (footprint "eagle-import:R0805")
      (libsource (lib "eagle-import") (part "R-EU_R0805"))
    )
    (comp (ref "R48")
      (value "3K6")
      (footprint "eagle-import:R0805")
      (libsource (lib "eagle-import") (part "R-EU_R0805"))
    )
    (comp (ref "R49")
      (value "120R")
      (footprint "eagle-import:R0805")
      (libsource (lib "eagle-import") (part "R-EU_R0805"))
    )
    (comp (ref "R50")
      (value "11K8")
      (footprint "eagle-import:R0805")
      (libsource (lib "eagle-import") (part "R-EU_R0805"))
    )
    (comp (ref "R51")
      (value "15K")
      (footprint "eagle-import:R0805")
      (libsource (lib "eagle-import") (part "R-EU_R0805"))
    )
    (comp (ref "SH3")
      (value "SHORTNOHOLE")
      (footprint "eagle-import:SHORT_NOHOLE")
      (libsource (lib "eagle-import") (part "SHORTNOHOLE"))
    )
    (comp (ref "X4")
      (value "DS1024-2*5R0")
      (footprint "eagle-import:SSW-105-02-T-D-RA")
      (libsource (lib "eagle-import") (part "SSW-105-02-T-D-RA"))
    )
    (comp (ref "ZD2")
      (value "MM3Z2V4T1G")
      (footprint "eagle-import:SOD323-W")
      (libsource (lib "eagle-import") (part "ZENER-DIODESOD323"))
    )
    (comp (ref "ZD3")
      (value "SMAJ51A")
      (footprint "eagle-import:DO214AA")
      (libsource (lib "eagle-import") (part "P6SMB68A"))
    )
    (comp (ref "C24")
      (value "100n")
      (footprint "eagle-import:C0603")
      (libsource (lib "eagle-import") (part "C-EUC0603"))
    )
    (comp (ref "C25")
      (value "N.C.")
      (footprint "eagle-import:C0603")
      (libsource (lib "eagle-import") (part "C-EUC0603"))
    )
    (comp (ref "C26")
      (value "100n")
      (footprint "eagle-import:C0603")
      (libsource (lib "eagle-import") (part "C-EUC0603"))
    )
    (comp (ref "C27")
      (value "100n")
      (footprint "eagle-import:C0603")
      (libsource (lib "eagle-import") (part "C-EUC0603"))
    )
    (comp (ref "C28")
      (value "100n")
      (footprint "eagle-import:C0603")
      (libsource (lib "eagle-import") (part "C-EUC0603"))
    )
    (comp (ref "C29")
      (value "4u7")
      (footprint "eagle-import:C1206")
      (libsource (lib "eagle-import") (part "C-EUC1206"))
    )
    (comp (ref "C30")
      (value "100n")
      (footprint "eagle-import:C0603")
      (libsource (lib "eagle-import") (part "C-EUC0603"))
    )
    (comp (ref "C31")
      (value "100n")
      (footprint "eagle-import:C0603")
      (libsource (lib "eagle-import") (part "C-EUC0603"))
    )
    (comp (ref "C32")
      (value "4p7")
      (footprint "eagle-import:C0603")
      (libsource (lib "eagle-import") (part "C-EUC0603"))
    )
    (comp (ref "C33")
      (value "4p7")
      (footprint "eagle-import:C0603")
      (libsource (lib "eagle-import") (part "C-EUC0603"))
    )
    (comp (ref "C34")
      (value "10n")
      (footprint "eagle-import:C0805")
      (libsource (lib "eagle-import") (part "C-EUC0805"))
    )
    (comp (ref "C35")
      (value "10n")
      (footprint "eagle-import:C0805")
      (libsource (lib "eagle-import") (part "C-EUC0805"))
    )
    (comp (ref "C36")
      (value "1n")
      (footprint "eagle-import:C0805")
      (libsource (lib "eagle-import") (part "C-EUC0805"))
    )
    (comp (ref "C37")
      (value "100n")
      (footprint "eagle-import:C0603")
      (libsource (lib "eagle-import") (part "C-EUC0603"))
    )
    (comp (ref "C38")
      (value "1u")
      (footprint "eagle-import:C0805")
      (libsource (lib "eagle-import") (part "C-EUC0805"))
    )
    (comp (ref "C39")
      (value "4n7")
      (footprint "eagle-import:C0805")
      (libsource (lib "eagle-import") (part "C-EUC0805"))
    )
    (comp (ref "C40")
      (value "100n")
      (footprint "eagle-import:C0603")
      (libsource (lib "eagle-import") (part "C-EUC0603"))
    )
    (comp (ref "C41")
      (value "4n7")
      (footprint "eagle-import:C0805")
      (libsource (lib "eagle-import") (part "C-EUC0805"))
    )
    (comp (ref "C42")
      (value "4n7")
      (footprint "eagle-import:C0805")
      (libsource (lib "eagle-import") (part "C-EUC0805"))
    )
    (comp (ref "C43")
      (value "4n7")
      (footprint "eagle-import:C0805")
      (libsource (lib "eagle-import") (part "C-EUC0805"))
    )
    (comp (ref "C44")
      (value "4n7")
      (footprint "eagle-import:C0805")
      (libsource (lib "eagle-import") (part "C-EUC0805"))
    )
    (comp (ref "FB1")
      (value "60R@100MHz")
      (footprint "eagle-import:BEAD0603")
      (libsource (lib "eagle-import") (part "FERRITE_BEAD0603"))
    )
    (comp (ref "IC6")
      (value "74HC2G04GW,125")
      (footprint "eagle-import:SOT65P210X110-6N")
      (libsource (lib "eagle-import") (part "74HC2G04"))
    )
    (comp (ref "IC7")
      (value "N.C.")
      (footprint "eagle-import:DRL6")
      (libsource (lib "eagle-import") (part "TPD4E001-DRL"))
    )
    (comp (ref "IC8")
      (value "STM32F373C8T6")
      (footprint "eagle-import:LQFP-48")
      (libsource (lib "eagle-import") (part "STM32F373C8T6"))
    )
    (comp (ref "IC9")
      (value "TL431B")
      (footprint "eagle-import:SOT103P240X110-3N")
      (libsource (lib "eagle-import") (part "TL431"))
    )
    (comp (ref "I_SET1")
      (value "JP2-NOCUT")
      (footprint "eagle-import:JP2-NOCUT")
      (libsource (lib "eagle-import") (part "JP2-NOCUT"))
    )
    (comp (ref "I_SET2")
      (value "JP2-NOCUT")
      (footprint "eagle-import:JP2-NOCUT")
      (libsource (lib "eagle-import") (part "JP2-NOCUT"))
    )
    (comp (ref "JP1")
      (value "JUMPER-2PIN-2MM")
      (footprint "eagle-import:2MM-2")
      (libsource (lib "eagle-import") (part "JUMPER-2PIN-2MM"))
    )
    (comp (ref "JP2")
      (value "JP2-CUT")
      (footprint "eagle-import:JP2-CUT")
      (libsource (lib "eagle-import") (part "JP2-CUT"))
    )
    (comp (ref "JP3")
      (value "JP2-NOCUT")
      (footprint "eagle-import:JP2-NOCUT")
      (libsource (lib "eagle-import") (part "JP2-NOCUT"))
    )
    (comp (ref "NTC1")
      (value "NTCS0805E3103JMT")
      (footprint "eagle-import:R_0805")
      (libsource (lib "eagle-import") (part "NTCR_0805"))
    )
    (comp (ref "NTC2")
      (value "NTCS0805E3103JMT")
      (footprint "eagle-import:R_0805")
      (libsource (lib "eagle-import") (part "NTCR_0805"))
    )
    (comp (ref "OE#1")
      (value "JP2-NOCUT")
      (footprint "eagle-import:JP2-NOCUT")
      (libsource (lib "eagle-import") (part "JP2-NOCUT"))
    )
    (comp (ref "OE#2")
      (value "JP2-NOCUT")
      (footprint "eagle-import:JP2-NOCUT")
      (libsource (lib "eagle-import") (part "JP2-NOCUT"))
    )
    (comp (ref "R14")
      (value "10K")
      (footprint "eagle-import:R0805")
      (libsource (lib "eagle-import") (part "R-EU_R0805"))
    )
    (comp (ref "R15")
      (value "10K")
      (footprint "eagle-import:R0805")
      (libsource (lib "eagle-import") (part "R-EU_R0805"))
    )
    (comp (ref "R16")
      (value "10K")
      (footprint "eagle-import:R0805")
      (libsource (lib "eagle-import") (part "R-EU_R0805"))
    )
    (comp (ref "R17")
      (value "10K")
      (footprint "eagle-import:R0805")
      (libsource (lib "eagle-import") (part "R-EU_R0805"))
    )
    (comp (ref "R18")
      (value "10K")
      (footprint "eagle-import:R0805")
      (libsource (lib "eagle-import") (part "R-EU_R0805"))
    )
    (comp (ref "R19")
      (value "N.C.")
      (footprint "eagle-import:R0805")
      (libsource (lib "eagle-import") (part "R-EU_R0805"))
    )
    (comp (ref "R20")
      (value "10K")
      (footprint "eagle-import:R0805")
      (libsource (lib "eagle-import") (part "R-EU_R0805"))
    )
    (comp (ref "R21")
      (value "3K3")
      (footprint "eagle-import:R0805")
      (libsource (lib "eagle-import") (part "R-EU_R0805"))
    )
    (comp (ref "R22")
      (value "3K3")
      (footprint "eagle-import:R0805")
      (libsource (lib "eagle-import") (part "R-EU_R0805"))
    )
    (comp (ref "R23")
      (value "120R")
      (footprint "eagle-import:R0805")
      (libsource (lib "eagle-import") (part "R-EU_R0805"))
    )
    (comp (ref "R24")
      (value "2K2")
      (footprint "eagle-import:R0805")
      (libsource (lib "eagle-import") (part "R-EU_R0805"))
    )
    (comp (ref "R25")
      (value "2K2")
      (footprint "eagle-import:R0805")
      (libsource (lib "eagle-import") (part "R-EU_R0805"))
    )
    (comp (ref "R26")
      (value "2K2")
      (footprint "eagle-import:R0805")
      (libsource (lib "eagle-import") (part "R-EU_R0805"))
    )
    (comp (ref "R27")
      (value "2K2")
      (footprint "eagle-import:R0805")
      (libsource (lib "eagle-import") (part "R-EU_R0805"))
    )
    (comp (ref "RN2")
      (value "N.C.")
      (footprint "eagle-import:CAY16")
      (libsource (lib "eagle-import") (part "R_ARRAY4"))
    )
    (comp (ref "SH2")
      (value "SHORTNOHOLE")
      (footprint "eagle-import:SHORT_NOHOLE")
      (libsource (lib "eagle-import") (part "SHORTNOHOLE"))
    )
    (comp (ref "U_SET1")
      (value "JP2-NOCUT")
      (footprint "eagle-import:JP2-NOCUT")
      (libsource (lib "eagle-import") (part "JP2-NOCUT"))
    )
    (comp (ref "U_SET2")
      (value "JP2-NOCUT")
      (footprint "eagle-import:JP2-NOCUT")
      (libsource (lib "eagle-import") (part "JP2-NOCUT"))
    )
    (comp (ref "X3")
      (value "N.C.")
      (footprint "eagle-import:22-23-2061")
      (fields (field (name "MF") "MOLEX") (field (name "MPN") "22-23-2061"))
      (libsource (lib "eagle-import") (part "22-23-2061"))
    )
    (comp (ref "Y1")
      (value "LF XTAL026392")
      (footprint "eagle-import:12SMX(B)")
      (libsource (lib "eagle-import") (part "XTAL7.5X5.1-B"))
    )
  )
  (nets
    (net (code "1") (name "+3V3") (class "Default")
      (node (ref "C18") (pin "2") (pinfunction "2_2") (pintype "passive"))
      (node (ref "C21") (pin "1") (pinfunction "1_1") (pintype "passive"))
      (node (ref "C25") (pin "1") (pinfunction "1_1") (pintype "passive"))
      (node (ref "C27") (pin "1") (pinfunction "1_1") (pintype "passive"))
      (node (ref "C28") (pin "2") (pinfunction "2_2") (pintype "passive"))
      (node (ref "C29") (pin "1") (pinfunction "1_1") (pintype "passive"))
      (node (ref "C36") (pin "2") (pinfunction "2_2") (pintype "passive"))
      (node (ref "C40") (pin "2") (pinfunction "2_2") (pintype "passive"))
      (node (ref "C47") (pin "1") (pinfunction "1_1") (pintype "passive"))
      (node (ref "C8") (pin "2") (pinfunction "2_2") (pintype "passive"))
      (node (ref "FB1") (pin "P$1") (pinfunction "1_P$1") (pintype "passive"))
      (node (ref "IC1") (pin "16") (pinfunction "VDD2_16") (pintype "passive"))
      (node (ref "IC12") (pin "4") (pinfunction "V+_4") (pintype "power_in"))
      (node (ref "IC3") (pin "10") (pinfunction "EN2_10") (pintype "input"))
      (node (ref "IC3") (pin "16") (pinfunction "VDD2_16") (pintype "passive"))
      (node (ref "IC5") (pin "5") (pinfunction "OUT_5") (pintype "passive"))
      (node (ref "IC6") (pin "5") (pinfunction "V+_5") (pintype "power_in"))
      (node (ref "IC7") (pin "6") (pinfunction "VCC_6") (pintype "passive"))
      (node (ref "IC8") (pin "17") (pinfunction "VDD_2_17") (pintype "passive"))
      (node (ref "IC8") (pin "48") (pinfunction "VDD_1_48") (pintype "bidirectional"))
      (node (ref "JP1") (pin "1") (pinfunction "1_1") (pintype "passive"))
      (node (ref "JP2") (pin "1") (pinfunction "1_1") (pintype "passive"))
      (node (ref "NTC1") (pin "1") (pinfunction "P$1_1") (pintype "bidirectional"))
      (node (ref "NTC2") (pin "1") (pinfunction "P$1_1") (pintype "bidirectional"))
      (node (ref "Q10") (pin "2") (pinfunction "S_2") (pintype "passive"))
      (node (ref "Q5") (pin "2") (pinfunction "S_2") (pintype "passive"))
      (node (ref "R20") (pin "1") (pinfunction "1_1") (pintype "passive"))
      (node (ref "R23") (pin "1") (pinfunction "1_1") (pintype "passive"))
    )
    (net (code "2") (name "+8V") (class "Default")
      (node (ref "C14") (pin "1") (pinfunction "1_1") (pintype "passive"))
      (node (ref "C22") (pin "2") (pinfunction "2_2") (pintype "passive"))
      (node (ref "C45") (pin "1") (pinfunction "1_1") (pintype "passive"))
      (node (ref "D10") (pin "A") (pinfunction "A_A") (pintype "passive"))
      (node (ref "D5") (pin "A") (pinfunction "A_A") (pintype "passive"))
      (node (ref "IC10") (pin "8") (pinfunction "V+_8") (pintype "power_in"))
      (node (ref "IC5") (pin "1") (pinfunction "IN_1") (pintype "input"))
      (node (ref "IC5") (pin "3") (pinfunction "ON/~{OFF}_3") (pintype "input"))
      (node (ref "R4") (pin "1") (pinfunction "1_1") (pintype "passive"))
    )
    (net (code "3") (name "+VAUX") (class "Default")
      (node (ref "X2") (pin "2") (pinfunction "1_2") (pintype "passive"))
    )
    (net (code "4") (name "+VREF") (class "Default")
      (node (ref "C39") (pin "2") (pinfunction "2_2") (pintype "passive"))
      (node (ref "IC8") (pin "25") (pinfunction "VREFSD+_25") (pintype "passive"))
      (node (ref "IC9") (pin "1") (pinfunction "C_1") (pintype "passive"))
      (node (ref "IC9") (pin "2") (pinfunction "R_2") (pintype "passive"))
      (node (ref "R23") (pin "2") (pinfunction "2_2") (pintype "passive"))
    )
    (net (code "5") (name "-8V") (class "Default")
      (node (ref "C5") (pin "1") (pinfunction "1_1") (pintype "passive"))
      (node (ref "C51") (pin "2") (pinfunction "2_2") (pintype "passive"))
      (node (ref "IC10") (pin "4") (pinfunction "V-_4") (pintype "power_in"))
      (node (ref "R2") (pin "1") (pinfunction "1_1") (pintype "passive"))
    )
    (net (code "6") (name "AGND") (class "Default")
      (node (ref "C39") (pin "1") (pinfunction "1_1") (pintype "passive"))
      (node (ref "IC8") (pin "23") (pinfunction "VSSSD/VREFSD-_23") (pintype "passive"))
      (node (ref "IC8") (pin "8") (pinfunction "VSSA/VREF-_8") (pintype "passive"))
      (node (ref "SH2") (pin "1") (pinfunction "GND_A_1") (pintype "bidirectional"))
    )
    (net (code "7") (name "BOOT0") (class "Default")
      (node (ref "IC3") (pin "13") (pinfunction "B2_13") (pintype "output"))
      (node (ref "IC8") (pin "44") (pinfunction "BOOT0_44") (pintype "input"))
      (node (ref "JP1") (pin "2") (pinfunction "2_2") (pintype "passive"))
      (node (ref "R15") (pin "2") (pinfunction "2_2") (pintype "passive"))
    )
    (net (code "8") (name "CC#1") (class "Default")
      (node (ref "IC12") (pin "7") (pinfunction "OUT_7") (pintype "output"))
      (node (ref "IC8") (pin "3") (pinfunction "PC14-OSC32_IN_3") (pintype "bidirectional"))
    )
    (net (code "9") (name "CC#2") (class "Default")
      (node (ref "IC12") (pin "1") (pinfunction "OUT_1") (pintype "output"))
      (node (ref "IC8") (pin "4") (pinfunction "PC15-OSC32_OUT_4") (pintype "bidirectional"))
    )
    (net (code "10") (name "CC_LED#1") (class "Default")
      (node (ref "IC8") (pin "2") (pinfunction "PC13_2") (pintype "bidirectional"))
      (node (ref "Q5") (pin "1") (pinfunction "G_1") (pintype "passive"))
      (node (ref "R49") (pin "2") (pinfunction "2_2") (pintype "passive"))
    )
    (net (code "11") (name "CC_LED#2") (class "Default")
      (node (ref "IC8") (pin "11") (pinfunction "PA1_11") (pintype "bidirectional"))
      (node (ref "Q10") (pin "1") (pinfunction "G_1") (pintype "passive"))
      (node (ref "R73") (pin "2") (pinfunction "2_2") (pintype "passive"))
    )
    (net (code "12") (name "DC_OUT+") (class "Default")
      (node (ref "C3") (pin "2") (pinfunction "2_2") (pintype "passive"))
      (node (ref "C46") (pin "+") (pinfunction "+_+") (pintype "passive"))
      (node (ref "C50") (pin "1") (pinfunction "1_1") (pintype "passive"))
      (node (ref "C52") (pin "1") (pinfunction "1_1") (pintype "passive"))
      (node (ref "C6") (pin "1") (pinfunction "1_1") (pintype "passive"))
      (node (ref "C68") (pin "+") (pinfunction "+_+") (pintype "passive"))
      (node (ref "C71") (pin "1") (pinfunction "1_1") (pintype "passive"))
      (node (ref "C72") (pin "1") (pinfunction "1_1") (pintype "passive"))
      (node (ref "C9") (pin "1") (pinfunction "1_1") (pintype "passive"))
      (node (ref "IC11") (pin "6") (pinfunction "IVINN_6") (pintype "input"))
      (node (ref "IC11") (pin "7") (pinfunction "IVINP_7") (pintype "input"))
      (node (ref "IC13") (pin "6") (pinfunction "IVINN_6") (pintype "input"))
      (node (ref "IC13") (pin "7") (pinfunction "IVINP_7") (pintype "input"))
      (node (ref "IC2") (pin "2") (pinfunction "VIN_2") (pintype "power_in"))
      (node (ref "L1") (pin "4") (pinfunction "2_4") (pintype "passive"))
      (node (ref "Q2") (pin "2") (pinfunction "D_2") (pintype "passive"))
      (node (ref "Q7") (pin "2") (pinfunction "D_2") (pintype "passive"))
      (node (ref "R28") (pin "1") (pinfunction "1_1") (pintype "passive"))
      (node (ref "R29") (pin "1") (pinfunction "1_1") (pintype "passive"))
      (node (ref "R3") (pin "2") (pinfunction "2_2") (pintype "passive"))
      (node (ref "R52") (pin "1") (pinfunction "1_1") (pintype "passive"))
      (node (ref "R53") (pin "1") (pinfunction "1_1") (pintype "passive"))
      (node (ref "ZD1") (pin "C") (pinfunction "C_C") (pintype "passive"))
    )
    (net (code "13") (name "DC_OUT-") (class "Default")
      (node (ref "C2") (pin "1") (pinfunction "1_1") (pintype "passive"))
      (node (ref "C46") (pin "-") (pinfunction "-_-") (pintype "passive"))
      (node (ref "C50") (pin "2") (pinfunction "2_2") (pintype "passive"))
      (node (ref "C52") (pin "2") (pinfunction "2_2") (pintype "passive"))
      (node (ref "C57") (pin "2") (pinfunction "2_2") (pintype "passive"))
      (node (ref "C59") (pin "2") (pinfunction "2_2") (pintype "passive"))
      (node (ref "C60") (pin "2") (pinfunction "2_2") (pintype "passive"))
      (node (ref "C61") (pin "2") (pinfunction "-_2") (pintype "passive"))
      (node (ref "C62") (pin "-") (pinfunction "-_-") (pintype "passive"))
      (node (ref "C63") (pin "2") (pinfunction "2_2") (pintype "passive"))
      (node (ref "C68") (pin "-") (pinfunction "-_-") (pintype "passive"))
      (node (ref "C71") (pin "2") (pinfunction "2_2") (pintype "passive"))
      (node (ref "C72") (pin "2") (pinfunction "2_2") (pintype "passive"))
      (node (ref "C77") (pin "2") (pinfunction "2_2") (pintype "passive"))
      (node (ref "C79") (pin "2") (pinfunction "2_2") (pintype "passive"))
      (node (ref "C80") (pin "2") (pinfunction "2_2") (pintype "passive"))
      (node (ref "C81") (pin "2") (pinfunction "-_2") (pintype "passive"))
      (node (ref "C82") (pin "-") (pinfunction "-_-") (pintype "passive"))
      (node (ref "C83") (pin "2") (pinfunction "2_2") (pintype "passive"))
      (node (ref "CH1") (pin "GND") (pinfunction "GND_GND") (pintype "bidirectional"))
      (node (ref "CH2") (pin "GND") (pinfunction "GND_GND") (pintype "bidirectional"))
      (node (ref "D12") (pin "A") (pinfunction "A_A") (pintype "passive"))
      (node (ref "D7") (pin "A") (pinfunction "A_A") (pintype "passive"))
      (node (ref "J3") (pin "1") (pinfunction "1_1") (pintype "passive"))
      (node (ref "J3") (pin "1.1") (pinfunction "1_1.1") (pintype "passive"))
      (node (ref "J5") (pin "1") (pinfunction "1_1") (pintype "passive"))
      (node (ref "J5") (pin "1.1") (pinfunction "1_1.1") (pintype "passive"))
      (node (ref "L1") (pin "2") (pinfunction "2_2") (pintype "passive"))
      (node (ref "LED1") (pin "CC") (pinfunction "C_CC") (pintype "passive"))
      (node (ref "LED2") (pin "CC") (pinfunction "C_CC") (pintype "passive"))
      (node (ref "Q3") (pin "3") (pinfunction "S_3") (pintype "passive"))
      (node (ref "Q8") (pin "3") (pinfunction "S_3") (pintype "passive"))
      (node (ref "R37") (pin "1") (pinfunction "1_1") (pintype "passive"))
      (node (ref "R41") (pin "2") (pinfunction "2_2") (pintype "passive"))
      (node (ref "R61") (pin "1") (pinfunction "1_1") (pintype "passive"))
      (node (ref "R65") (pin "2") (pinfunction "2_2") (pintype "passive"))
      (node (ref "SH1") (pin "2") (pinfunction "GND_B_2") (pintype "bidirectional"))
      (node (ref "SH3") (pin "1") (pinfunction "GND_A_1") (pintype "bidirectional"))
      (node (ref "SH4") (pin "1") (pinfunction "GND_A_1") (pintype "bidirectional"))
      (node (ref "X4") (pin "1") (pinfunction "1_1") (pintype "passive"))
      (node (ref "X4") (pin "10") (pinfunction "1_10") (pintype "passive"))
      (node (ref "X4") (pin "2") (pinfunction "1_2") (pintype "passive"))
      (node (ref "X4") (pin "3") (pinfunction "1_3") (pintype "passive"))
      (node (ref "X4") (pin "4") (pinfunction "1_4") (pintype "passive"))
      (node (ref "X4") (pin "5") (pinfunction "1_5") (pintype "passive"))
      (node (ref "X4") (pin "6") (pinfunction "1_6") (pintype "passive"))
      (node (ref "X4") (pin "7") (pinfunction "1_7") (pintype "passive"))
      (node (ref "X4") (pin "8") (pinfunction "1_8") (pintype "passive"))
      (node (ref "X4") (pin "9") (pinfunction "1_9") (pintype "passive"))
      (node (ref "ZD1") (pin "A") (pinfunction "A_A") (pintype "passive"))
      (node (ref "ZD3") (pin "A") (pinfunction "A_A") (pintype "passive"))
      (node (ref "ZD5") (pin "A") (pinfunction "A_A") (pintype "passive"))
    )
    (net (code "14") (name "DIB_5V") (class "Default")
      (node (ref "X2") (pin "23") (pinfunction "1_23") (pintype "passive"))
      (node (ref "X2") (pin "24") (pinfunction "1_24") (pintype "passive"))
    )
    (net (code "15") (name "DIB_12V") (class "Default")
      (node (ref "X2") (pin "21") (pinfunction "1_21") (pintype "passive"))
      (node (ref "X2") (pin "22") (pinfunction "1_22") (pintype "passive"))
    )
    (net (code "16") (name "DIB_A0") (class "Default")
      (node (ref "IC4") (pin "1") (pinfunction "A0_1") (pintype "input"))
      (node (ref "R13") (pin "2") (pinfunction "2_2") (pintype "passive"))
      (node (ref "X2") (pin "17") (pinfunction "1_17") (pintype "passive"))
    )
    (net (code "17") (name "DIB_A1") (class "Default")
      (node (ref "IC4") (pin "2") (pinfunction "A1_2") (pintype "input"))
      (node (ref "R12") (pin "2") (pinfunction "2_2") (pintype "passive"))
      (node (ref "X2") (pin "19") (pinfunction "1_19") (pintype "passive"))
    )
    (net (code "18") (name "DIB_A2") (class "Default")
      (node (ref "IC4") (pin "3") (pinfunction "A2_3") (pintype "input"))
      (node (ref "R11") (pin "2") (pinfunction "2_2") (pintype "passive"))
      (node (ref "X2") (pin "18") (pinfunction "1_18") (pintype "passive"))
    )
    (net (code "19") (name "DIB_BOOT0") (class "Default")
      (node (ref "IC3") (pin "4") (pinfunction "A2_4") (pintype "input"))
      (node (ref "X2") (pin "26") (pinfunction "1_26") (pintype "passive"))
    )
    (net (code "20") (name "DIB_CSA") (class "Default")
      (node (ref "IC1") (pin "5") (pinfunction "A4_5") (pintype "input"))
      (node (ref "X2") (pin "9") (pinfunction "1_9") (pintype "passive"))
    )
    (net (code "21") (name "DIB_CSB") (class "Default")
      (node (ref "X2") (pin "12") (pinfunction "1_12") (pintype "passive"))
    )
    (net (code "22") (name "DIB_IRQ") (class "Default")
      (node (ref "IC1") (pin "7") (pinfunction "A6_7") (pintype "output"))
      (node (ref "X2") (pin "10") (pinfunction "1_10") (pintype "passive"))
    )
    (net (code "23") (name "DIB_MISO") (class "Default")
      (node (ref "IC1") (pin "6") (pinfunction "A5_6") (pintype "output"))
      (node (ref "X2") (pin "14") (pinfunction "1_14") (pintype "passive"))
    )
    (net (code "24") (name "DIB_MOSI") (class "Default")
      (node (ref "IC3") (pin "3") (pinfunction "A1_3") (pintype "input"))
      (node (ref "X2") (pin "15") (pinfunction "1_15") (pintype "passive"))
    )
    (net (code "25") (name "DIB_NFAULT") (class "Default")
      (node (ref "X2") (pin "3") (pinfunction "1_3") (pintype "passive"))
    )
    (net (code "26") (name "DIB_NRESET") (class "Default")
      (node (ref "IC1") (pin "2") (pinfunction "A1_2") (pintype "input"))
      (node (ref "X2") (pin "4") (pinfunction "1_4") (pintype "passive"))
    )
    (net (code "27") (name "DIB_SCL") (class "Default")
      (node (ref "IC4") (pin "6") (pinfunction "SCL_6") (pintype "bidirectional"))
      (node (ref "X2") (pin "5") (pinfunction "1_5") (pintype "passive"))
    )
    (net (code "28") (name "DIB_SCLK") (class "Default")
      (node (ref "IC1") (pin "4") (pinfunction "A3_4") (pintype "input"))
      (node (ref "X2") (pin "13") (pinfunction "1_13") (pintype "passive"))
    )
    (net (code "29") (name "DIB_SDA") (class "Default")
      (node (ref "IC4") (pin "5") (pinfunction "SDA_5") (pintype "bidirectional"))
      (node (ref "X2") (pin "8") (pinfunction "1_8") (pintype "passive"))
    )
    (net (code "30") (name "DIB_SYNC") (class "Default")
      (node (ref "IC1") (pin "3") (pinfunction "A2_3") (pintype "input"))
      (node (ref "X2") (pin "6") (pinfunction "1_6") (pintype "passive"))
    )
    (net (code "31") (name "DIB_UART_RX") (class "Default")
      (node (ref "IC3") (pin "6") (pinfunction "A4_6") (pintype "output"))
      (node (ref "X2") (pin "28") (pinfunction "1_28") (pintype "passive"))
    )
    (net (code "32") (name "DIB_UART_TX") (class "Default")
      (node (ref "IC3") (pin "5") (pinfunction "A3_5") (pintype "input"))
      (node (ref "X2") (pin "27") (pinfunction "1_27") (pintype "passive"))
    )
    (net (code "33") (name "FB1") (class "Default")
      (node (ref "IC11") (pin "11") (pinfunction "FB_11") (pintype "input"))
      (node (ref "IC12") (pin "10") (pinfunction "+IN_10") (pintype "input"))
      (node (ref "R39") (pin "1") (pinfunction "1_1") (pintype "passive"))
      (node (ref "R46") (pin "2") (pinfunction "2_2") (pintype "passive"))
      (node (ref "R48") (pin "2") (pinfunction "2_2") (pintype "passive"))
    )
    (net (code "34") (name "FB2") (class "Default")
      (node (ref "IC12") (pin "12") (pinfunction "+IN_12") (pintype "input"))
      (node (ref "IC13") (pin "11") (pinfunction "FB_11") (pintype "input"))
      (node (ref "R63") (pin "1") (pinfunction "1_1") (pintype "passive"))
      (node (ref "R70") (pin "2") (pinfunction "2_2") (pintype "passive"))
      (node (ref "R72") (pin "2") (pinfunction "2_2") (pintype "passive"))
    )
    (net (code "35") (name "GND") (class "Default")
      (node (ref "C12") (pin "2") (pinfunction "2_2") (pintype "passive"))
      (node (ref "C13") (pin "2") (pinfunction "2_2") (pintype "passive"))
      (node (ref "C14") (pin "2") (pinfunction "2_2") (pintype "passive"))
      (node (ref "C15") (pin "2") (pinfunction "2_2") (pintype "passive"))
      (node (ref "C16") (pin "1") (pinfunction "1_1") (pintype "passive"))
      (node (ref "C18") (pin "1") (pinfunction "1_1") (pintype "passive"))
      (node (ref "C19") (pin "1") (pinfunction "1_1") (pintype "passive"))
      (node (ref "C21") (pin "2") (pinfunction "2_2") (pintype "passive"))
      (node (ref "C22") (pin "1") (pinfunction "1_1") (pintype "passive"))
      (node (ref "C23") (pin "1") (pinfunction "1_1") (pintype "passive"))
      (node (ref "C25") (pin "2") (pinfunction "2_2") (pintype "passive"))
      (node (ref "C26") (pin "2") (pinfunction "2_2") (pintype "passive"))
      (node (ref "C27") (pin "2") (pinfunction "2_2") (pintype "passive"))
      (node (ref "C28") (pin "1") (pinfunction "1_1") (pintype "passive"))
      (node (ref "C29") (pin "2") (pinfunction "2_2") (pintype "passive"))
      (node (ref "C31") (pin "2") (pinfunction "2_2") (pintype "passive"))
      (node (ref "C32") (pin "1") (pinfunction "1_1") (pintype "passive"))
      (node (ref "C33") (pin "1") (pinfunction "1_1") (pintype "passive"))
      (node (ref "C34") (pin "1") (pinfunction "1_1") (pintype "passive"))
      (node (ref "C35") (pin "1") (pinfunction "1_1") (pintype "passive"))
      (node (ref "C37") (pin "1") (pinfunction "1_1") (pintype "passive"))
      (node (ref "C38") (pin "1") (pinfunction "1_1") (pintype "passive"))
      (node (ref "C4") (pin "2") (pinfunction "2_2") (pintype "passive"))
      (node (ref "C40") (pin "1") (pinfunction "1_1") (pintype "passive"))
      (node (ref "C41") (pin "1") (pinfunction "1_1") (pintype "passive"))
      (node (ref "C42") (pin "1") (pinfunction "1_1") (pintype "passive"))
      (node (ref "C43") (pin "1") (pinfunction "1_1") (pintype "passive"))
      (node (ref "C44") (pin "1") (pinfunction "1_1") (pintype "passive"))
      (node (ref "C45") (pin "2") (pinfunction "2_2") (pintype "passive"))
      (node (ref "C47") (pin "2") (pinfunction "2_2") (pintype "passive"))
      (node (ref "C49") (pin "2") (pinfunction "2_2") (pintype "passive"))
      (node (ref "C5") (pin "2") (pinfunction "2_2") (pintype "passive"))
      (node (ref "C51") (pin "1") (pinfunction "1_1") (pintype "passive"))
      (node (ref "C53") (pin "2") (pinfunction "2_2") (pintype "passive"))
      (node (ref "C55") (pin "2") (pinfunction "2_2") (pintype "passive"))
      (node (ref "C6") (pin "2") (pinfunction "2_2") (pintype "passive"))
      (node (ref "C64") (pin "1") (pinfunction "1_1") (pintype "passive"))
      (node (ref "C66") (pin "1") (pinfunction "1_1") (pintype "passive"))
      (node (ref "C70") (pin "2") (pinfunction "2_2") (pintype "passive"))
      (node (ref "C73") (pin "2") (pinfunction "2_2") (pintype "passive"))
      (node (ref "C75") (pin "2") (pinfunction "2_2") (pintype "passive"))
      (node (ref "C8") (pin "1") (pinfunction "1_1") (pintype "passive"))
      (node (ref "C84") (pin "1") (pinfunction "1_1") (pintype "passive"))
      (node (ref "C86") (pin "1") (pinfunction "1_1") (pintype "passive"))
      (node (ref "C9") (pin "2") (pinfunction "2_2") (pintype "passive"))
      (node (ref "D2") (pin "A") (pinfunction "A_A") (pintype "passive"))
      (node (ref "GND") (pin "1") (pinfunction "P$1_1") (pintype "bidirectional"))
      (node (ref "IC1") (pin "9") (pinfunction "GND2_9") (pintype "passive"))
      (node (ref "IC11") (pin "12") (pinfunction "GND_12") (pintype "passive"))
      (node (ref "IC11") (pin "21") (pinfunction "SYNC_21") (pintype "input"))
      (node (ref "IC11") (pin "23") (pinfunction "GND_23") (pintype "passive"))
      (node (ref "IC11") (pin "28") (pinfunction "GND_28") (pintype "passive"))
      (node (ref "IC11") (pin "TP") (pinfunction "GND_PAD_TP") (pintype "passive"))
      (node (ref "IC12") (pin "11") (pinfunction "V-_11") (pintype "power_in"))
      (node (ref "IC13") (pin "12") (pinfunction "GND_12") (pintype "passive"))
      (node (ref "IC13") (pin "21") (pinfunction "SYNC_21") (pintype "input"))
      (node (ref "IC13") (pin "23") (pinfunction "GND_23") (pintype "passive"))
      (node (ref "IC13") (pin "28") (pinfunction "GND_28") (pintype "passive"))
      (node (ref "IC13") (pin "TP") (pinfunction "GND_PAD_TP") (pintype "passive"))
      (node (ref "IC2") (pin "9") (pinfunction "GND_9") (pintype "passive"))
      (node (ref "IC2") (pin "TP") (pinfunction "TP_TP") (pintype "passive"))
      (node (ref "IC3") (pin "15") (pinfunction "GND2_15") (pintype "passive"))
      (node (ref "IC3") (pin "9") (pinfunction "GND2_2_9") (pintype "passive"))
      (node (ref "IC5") (pin "2") (pinfunction "GND_2") (pintype "passive"))
      (node (ref "IC6") (pin "2") (pinfunction "V-_2") (pintype "power_in"))
      (node (ref "IC7") (pin "3") (pinfunction "GND_3") (pintype "power_in"))
      (node (ref "IC8") (pin "47") (pinfunction "VSS_1_47") (pintype "bidirectional"))
      (node (ref "IC9") (pin "3") (pinfunction "A_3") (pintype "passive"))
      (node (ref "R10") (pin "1") (pinfunction "1_1") (pintype "passive"))
      (node (ref "R15") (pin "1") (pinfunction "1_1") (pintype "passive"))
      (node (ref "R19") (pin "1") (pinfunction "1_1") (pintype "passive"))
      (node (ref "R21") (pin "2") (pinfunction "2_2") (pintype "passive"))
      (node (ref "R22") (pin "2") (pinfunction "2_2") (pintype "passive"))
      (node (ref "R30") (pin "1") (pinfunction "1_1") (pintype "passive"))
      (node (ref "R33") (pin "1") (pinfunction "1_1") (pintype "passive"))
      (node (ref "R42") (pin "1") (pinfunction "1_1") (pintype "passive"))
      (node (ref "R45") (pin "1") (pinfunction "1_1") (pintype "passive"))
      (node (ref "R46") (pin "1") (pinfunction "1_1") (pintype "passive"))
      (node (ref "R47") (pin "1") (pinfunction "1_1") (pintype "passive"))
      (node (ref "R5") (pin "1") (pinfunction "1_1") (pintype "passive"))
      (node (ref "R51") (pin "1") (pinfunction "1_1") (pintype "passive"))
      (node (ref "R54") (pin "1") (pinfunction "1_1") (pintype "passive"))
      (node (ref "R57") (pin "1") (pinfunction "1_1") (pintype "passive"))
      (node (ref "R6") (pin "1") (pinfunction "1_1") (pintype "passive"))
      (node (ref "R66") (pin "1") (pinfunction "1_1") (pintype "passive"))
      (node (ref "R69") (pin "1") (pinfunction "1_1") (pintype "passive"))
      (node (ref "R70") (pin "1") (pinfunction "1_1") (pintype "passive"))
      (node (ref "R71") (pin "1") (pinfunction "1_1") (pintype "passive"))
      (node (ref "R75") (pin "1") (pinfunction "1_1") (pintype "passive"))
      (node (ref "R8") (pin "1") (pinfunction "1_1") (pintype "passive"))
      (node (ref "SH1") (pin "1") (pinfunction "GND_A_1") (pintype "bidirectional"))
      (node (ref "SH2") (pin "2") (pinfunction "GND_B_2") (pintype "bidirectional"))
      (node (ref "SH3") (pin "2") (pinfunction "GND_B_2") (pintype "bidirectional"))
      (node (ref "SH4") (pin "2") (pinfunction "GND_B_2") (pintype "bidirectional"))
      (node (ref "TR1") (pin "4") (pinfunction "4_4") (pintype "passive"))
      (node (ref "X3") (pin "3") (pinfunction "S_3") (pintype "passive"))
    )
    (net (code "36") (name "GNDIO") (class "Default")
      (node (ref "C17") (pin "2") (pinfunction "2_2") (pintype "passive"))
      (node (ref "C20") (pin "1") (pinfunction "1_1") (pintype "passive"))
      (node (ref "C7") (pin "2") (pinfunction "2_2") (pintype "passive"))
      (node (ref "IC1") (pin "8") (pinfunction "GND1_8") (pintype "passive"))
      (node (ref "IC3") (pin "2") (pinfunction "GND1_2_2") (pintype "passive"))
      (node (ref "IC3") (pin "8") (pinfunction "GND1_8") (pintype "passive"))
      (node (ref "IC4") (pin "4") (pinfunction "GND_4") (pintype "passive"))
      (node (ref "IC4") (pin "7") (pinfunction "WP_7") (pintype "input"))
      (node (ref "X2") (pin "11") (pinfunction "1_11") (pintype "passive"))
      (node (ref "X2") (pin "16") (pinfunction "1_16") (pintype "passive"))
      (node (ref "X2") (pin "20") (pinfunction "1_20") (pintype "passive"))
      (node (ref "X2") (pin "25") (pinfunction "1_25") (pintype "passive"))
      (node (ref "X2") (pin "7") (pinfunction "1_7") (pintype "passive"))
    )
    (net (code "37") (name "INTVCC1") (class "Default")
      (node (ref "C55") (pin "1") (pinfunction "1_1") (pintype "passive"))
      (node (ref "D6") (pin "A") (pinfunction "A_A") (pintype "passive"))
      (node (ref "IC11") (pin "2") (pinfunction "INTVCC_2") (pintype "passive"))
      (node (ref "R43") (pin "1") (pinfunction "1_1") (pintype "passive"))
      (node (ref "R44") (pin "2") (pinfunction "2_2") (pintype "passive"))
    )
    (net (code "38") (name "INTVCC2") (class "Default")
      (node (ref "C75") (pin "1") (pinfunction "1_1") (pintype "passive"))
      (node (ref "D11") (pin "A") (pinfunction "A_A") (pintype "passive"))
      (node (ref "IC13") (pin "2") (pinfunction "INTVCC_2") (pintype "passive"))
      (node (ref "R67") (pin "1") (pinfunction "1_1") (pintype "passive"))
      (node (ref "R68") (pin "2") (pinfunction "2_2") (pintype "passive"))
    )
    (net (code "39") (name "IRQ") (class "Default")
      (node (ref "IC1") (pin "10") (pinfunction "B6_10") (pintype "input"))
      (node (ref "IC8") (pin "33") (pinfunction "PA12_33") (pintype "bidirectional"))
    )
    (net (code "40") (name "I_MON#1") (class "Default")
      (node (ref "C42") (pin "2") (pinfunction "2_2") (pintype "passive"))
      (node (ref "IC8") (pin "19") (pinfunction "PB1_19") (pintype "bidirectional"))
      (node (ref "R25") (pin "1") (pinfunction "1_1") (pintype "passive"))
    )
    (net (code "41") (name "I_MON#2") (class "Default")
      (node (ref "C44") (pin "2") (pinfunction "2_2") (pintype "passive"))
      (node (ref "IC8") (pin "21") (pinfunction "PE8_21") (pintype "bidirectional"))
      (node (ref "R27") (pin "1") (pinfunction "1_1") (pintype "passive"))
    )
    (net (code "42") (name "I_MON1") (class "Default")
      (node (ref "C64") (pin "2") (pinfunction "2_2") (pintype "passive"))
      (node (ref "R25") (pin "2") (pinfunction "2_2") (pintype "passive"))
      (node (ref "R38") (pin "1") (pinfunction "1_1") (pintype "passive"))
    )
    (net (code "43") (name "I_MON2") (class "Default")
      (node (ref "C84") (pin "2") (pinfunction "2_2") (pintype "passive"))
      (node (ref "R27") (pin "2") (pinfunction "2_2") (pintype "passive"))
      (node (ref "R62") (pin "1") (pinfunction "1_1") (pintype "passive"))
    )
    (net (code "44") (name "I_SET#1") (class "Default")
      (node (ref "I_SET1") (pin "1") (pinfunction "1_1") (pintype "passive"))
      (node (ref "R32") (pin "1") (pinfunction "1_1") (pintype "passive"))
    )
    (net (code "45") (name "I_SET#2") (class "Default")
      (node (ref "I_SET2") (pin "1") (pinfunction "1_1") (pintype "passive"))
      (node (ref "R56") (pin "1") (pinfunction "1_1") (pintype "passive"))
    )
    (net (code "46") (name "I_SET_OUT#1") (class "Default")
      (node (ref "IC6") (pin "1") (pinfunction "I_1") (pintype "input"))
      (node (ref "IC8") (pin "45") (pinfunction "PB8_45") (pintype "bidirectional"))
      (node (ref "R14") (pin "2") (pinfunction "2_2") (pintype "passive"))
    )
    (net (code "47") (name "I_SET_OUT#2") (class "Default")
      (node (ref "IC6") (pin "3") (pinfunction "I_3") (pintype "input"))
      (node (ref "IC8") (pin "46") (pinfunction "PB9_46") (pintype "bidirectional"))
      (node (ref "R17") (pin "2") (pinfunction "2_2") (pintype "passive"))
    )
    (net (code "48") (name "MISO") (class "Default")
      (node (ref "IC1") (pin "11") (pinfunction "B5_11") (pintype "input"))
      (node (ref "IC8") (pin "30") (pinfunction "PA9_30") (pintype "bidirectional"))
    )
    (net (code "49") (name "MOSI") (class "Default")
      (node (ref "IC8") (pin "31") (pinfunction "PA10_31") (pintype "bidirectional"))
      (node (ref "RN1") (pin "5") (pinfunction "2_5") (pintype "passive"))
    )
    (net (code "50") (name "NRST") (class "Default")
      (node (ref "C36") (pin "1") (pinfunction "1_1") (pintype "passive"))
      (node (ref "IC8") (pin "7") (pinfunction "NRST_7") (pintype "input"))
      (node (ref "JP3") (pin "2") (pinfunction "2_2") (pintype "passive"))
      (node (ref "R20") (pin "2") (pinfunction "2_2") (pintype "passive"))
      (node (ref "RN2") (pin "3") (pinfunction "1_3") (pintype "passive"))
    )
    (net (code "51") (name "NSS") (class "Default")
      (node (ref "IC8") (pin "32") (pinfunction "PA11_32") (pintype "bidirectional"))
      (node (ref "RN1") (pin "6") (pinfunction "2_6") (pintype "passive"))
    )
    (net (code "52") (name "Net-(C4-Pad1)") (class "Default")
      (node (ref "C4") (pin "1") (pinfunction "1_1") (pintype "passive"))
      (node (ref "D1") (pin "A") (pinfunction "A_A") (pintype "passive"))
      (node (ref "R2") (pin "2") (pinfunction "2_2") (pintype "passive"))
    )
    (net (code "53") (name "Net-(C11-Pad2)") (class "Default")
      (node (ref "C11") (pin "2") (pinfunction "2_2") (pintype "passive"))
      (node (ref "R5") (pin "2") (pinfunction "2_2") (pintype "passive"))
    )
    (net (code "54") (name "Net-(C12-Pad1)") (class "Default")
      (node (ref "C12") (pin "1") (pinfunction "1_1") (pintype "passive"))
      (node (ref "C13") (pin "1") (pinfunction "1_1") (pintype "passive"))
      (node (ref "R4") (pin "2") (pinfunction "2_2") (pintype "passive"))
      (node (ref "R7") (pin "2") (pinfunction "2_2") (pintype "passive"))
      (node (ref "TR1") (pin "3") (pinfunction "3_3") (pintype "passive"))
    )
    (net (code "55") (name "Net-(C19-Pad2)") (class "Default")
      (node (ref "C19") (pin "2") (pinfunction "2_2") (pintype "passive"))
      (node (ref "R9") (pin "1") (pinfunction "1_1") (pintype "passive"))
    )
    (net (code "56") (name "Net-(C24-Pad1)") (class "Default")
      (node (ref "C24") (pin "1") (pinfunction "1_1") (pintype "passive"))
      (node (ref "C26") (pin "1") (pinfunction "1_1") (pintype "passive"))
      (node (ref "I_SET1") (pin "2") (pinfunction "2_2") (pintype "passive"))
      (node (ref "R14") (pin "1") (pinfunction "1_1") (pintype "passive"))
    )
    (net (code "57") (name "Net-(C24-Pad2)") (class "Default")
      (node (ref "C24") (pin "2") (pinfunction "2_2") (pintype "passive"))
      (node (ref "R16") (pin "1") (pinfunction "1_1") (pintype "passive"))
    )
    (net (code "58") (name "Net-(C30-Pad1)") (class "Default")
      (node (ref "C30") (pin "1") (pinfunction "1_1") (pintype "passive"))
      (node (ref "C31") (pin "1") (pinfunction "1_1") (pintype "passive"))
      (node (ref "I_SET2") (pin "2") (pinfunction "2_2") (pintype "passive"))
      (node (ref "R17") (pin "1") (pinfunction "1_1") (pintype "passive"))
    )
    (net (code "59") (name "Net-(C30-Pad2)") (class "Default")
      (node (ref "C30") (pin "2") (pinfunction "2_2") (pintype "passive"))
      (node (ref "R18") (pin "1") (pinfunction "1_1") (pintype "passive"))
    )
    (net (code "60") (name "Net-(C58-Pad2)") (class "Default")
      (node (ref "C58") (pin "2") (pinfunction "2_2") (pintype "passive"))
      (node (ref "R37") (pin "2") (pinfunction "2_2") (pintype "passive"))
    )
    (net (code "61") (name "Net-(C67-Pad1)") (class "Default")
      (node (ref "C67") (pin "1") (pinfunction "1_1") (pintype "passive"))
      (node (ref "R45") (pin "2") (pinfunction "2_2") (pintype "passive"))
    )
    (net (code "62") (name "Net-(C78-Pad2)") (class "Default")
      (node (ref "C78") (pin "2") (pinfunction "2_2") (pintype "passive"))
      (node (ref "R61") (pin "2") (pinfunction "2_2") (pintype "passive"))
    )
    (net (code "63") (name "Net-(C87-Pad1)") (class "Default")
      (node (ref "C87") (pin "1") (pinfunction "1_1") (pintype "passive"))
      (node (ref "R69") (pin "2") (pinfunction "2_2") (pintype "passive"))
    )
    (net (code "64") (name "Net-(D1-PadC)") (class "Default")
      (node (ref "D1") (pin "C") (pinfunction "C_C") (pintype "passive"))
      (node (ref "TR1") (pin "2") (pinfunction "2_2") (pintype "passive"))
    )
    (net (code "65") (name "Net-(IC1-B2)") (class "Default")
      (node (ref "IC1") (pin "14") (pinfunction "B2_14") (pintype "output"))
      (node (ref "RN1") (pin "1") (pinfunction "1_1") (pintype "passive"))
    )
    (net (code "66") (name "Net-(IC1-B3)") (class "Default")
      (node (ref "IC1") (pin "13") (pinfunction "B3_13") (pintype "output"))
      (node (ref "RN1") (pin "2") (pinfunction "1_2") (pintype "passive"))
    )
    (net (code "67") (name "Net-(IC1-B4)") (class "Default")
      (node (ref "IC1") (pin "12") (pinfunction "B4_12") (pintype "output"))
      (node (ref "RN1") (pin "3") (pinfunction "1_3") (pintype "passive"))
    )
    (net (code "68") (name "Net-(IC2-BOOT)") (class "Default")
      (node (ref "C10") (pin "2") (pinfunction "2_2") (pintype "passive"))
      (node (ref "IC2") (pin "1") (pinfunction "BOOT_1") (pintype "output"))
    )
    (net (code "69") (name "Net-(IC2-COMP)") (class "Default")
      (node (ref "C16") (pin "2") (pinfunction "2_2") (pintype "passive"))
      (node (ref "IC2") (pin "8") (pinfunction "COMP_8") (pintype "output"))
      (node (ref "R9") (pin "2") (pinfunction "2_2") (pintype "passive"))
    )
    (net (code "70") (name "Net-(IC2-EN)") (class "Default")
      (node (ref "IC2") (pin "3") (pinfunction "EN_3") (pintype "input"))
      (node (ref "R3") (pin "1") (pinfunction "1_1") (pintype "passive"))
      (node (ref "R6") (pin "2") (pinfunction "2_2") (pintype "passive"))
    )
    (net (code "71") (name "Net-(IC2-PH)") (class "Default")
      (node (ref "C10") (pin "1") (pinfunction "1_1") (pintype "passive"))
      (node (ref "C11") (pin "1") (pinfunction "1_1") (pintype "passive"))
      (node (ref "D2") (pin "C") (pinfunction "C_C") (pintype "passive"))
      (node (ref "IC2") (pin "10") (pinfunction "PH_10") (pintype "input"))
      (node (ref "TR1") (pin "1") (pinfunction "1_1") (pintype "passive"))
    )
    (net (code "72") (name "Net-(IC2-RT{slash}CLK)") (class "Default")
      (node (ref "IC2") (pin "5") (pinfunction "RT/CLK_5") (pintype "input"))
      (node (ref "R8") (pin "2") (pinfunction "2_2") (pintype "passive"))
    )
    (net (code "73") (name "Net-(IC2-SS{slash}TR)") (class "Default")
      (node (ref "C15") (pin "1") (pinfunction "1_1") (pintype "passive"))
      (node (ref "IC2") (pin "4") (pinfunction "SS/TR_4") (pintype "input"))
    )
    (net (code "74") (name "Net-(IC2-VSENSE)") (class "Default")
      (node (ref "IC2") (pin "7") (pinfunction "VSENSE_7") (pintype "input"))
      (node (ref "R10") (pin "2") (pinfunction "2_2") (pintype "passive"))
      (node (ref "R7") (pin "1") (pinfunction "1_1") (pintype "passive"))
    )
    (net (code "75") (name "Net-(IC3-B1)") (class "Default")
      (node (ref "IC3") (pin "14") (pinfunction "B1_14") (pintype "output"))
      (node (ref "RN1") (pin "4") (pinfunction "1_4") (pintype "passive"))
    )
    (net (code "76") (name "Net-(IC5-BYPASS)") (class "Default")
      (node (ref "C23") (pin "2") (pinfunction "2_2") (pintype "passive"))
      (node (ref "IC5") (pin "4") (pinfunction "BYPASS_4") (pintype "passive"))
    )
    (net (code "77") (name "Net-(IC6A-O)") (class "Default")
      (node (ref "IC6") (pin "6") (pinfunction "O_6") (pintype "output"))
      (node (ref "R16") (pin "2") (pinfunction "2_2") (pintype "passive"))
    )
    (net (code "78") (name "Net-(IC6B-O)") (class "Default")
      (node (ref "IC6") (pin "4") (pinfunction "O_4") (pintype "output"))
      (node (ref "R18") (pin "2") (pinfunction "2_2") (pintype "passive"))
    )
    (net (code "79") (name "Net-(IC7-IO1)") (class "Default")
      (node (ref "IC7") (pin "1") (pinfunction "IO1_1") (pintype "bidirectional"))
      (node (ref "RN2") (pin "8") (pinfunction "2_8") (pintype "passive"))
      (node (ref "X3") (pin "6") (pinfunction "S_6") (pintype "passive"))
    )
    (net (code "80") (name "Net-(IC7-IO2)") (class "Default")
      (node (ref "IC7") (pin "2") (pinfunction "IO2_2") (pintype "bidirectional"))
      (node (ref "RN2") (pin "6") (pinfunction "2_6") (pintype "passive"))
      (node (ref "X3") (pin "5") (pinfunction "S_5") (pintype "passive"))
    )
    (net (code "81") (name "Net-(IC8-PB5)") (class "Default")
      (node (ref "IC8") (pin "41") (pinfunction "PB5_41") (pintype "bidirectional"))
      (node (ref "OE#1") (pin "1") (pinfunction "1_1") (pintype "passive"))
    )
    (net (code "82") (name "Net-(IC8-PB6)") (class "Default")
      (node (ref "IC8") (pin "42") (pinfunction "PB6_42") (pintype "bidirectional"))
      (node (ref "OE#2") (pin "1") (pinfunction "1_1") (pintype "passive"))
    )
    (net (code "83") (name "Net-(IC8-PF0-OSC_IN)") (class "Default")
      (node (ref "C32") (pin "2") (pinfunction "2_2") (pintype "passive"))
      (node (ref "IC8") (pin "5") (pinfunction "PF0-OSC_IN_5") (pintype "bidirectional"))
      (node (ref "Y1") (pin "3") (pinfunction "2_3") (pintype "passive"))
    )
    (net (code "84") (name "Net-(IC8-PF1-OSC_OUT)") (class "Default")
      (node (ref "C33") (pin "2") (pinfunction "2_2") (pintype "passive"))
      (node (ref "IC8") (pin "6") (pinfunction "PF1-OSC_OUT_6") (pintype "bidirectional"))
      (node (ref "Y1") (pin "1") (pinfunction "1_1") (pintype "passive"))
    )
    (net (code "85") (name "Net-(IC10A-+IN)") (class "Default")
      (node (ref "IC10") (pin "3") (pinfunction "+IN_3") (pintype "input"))
      (node (ref "R56") (pin "2") (pinfunction "2_2") (pintype "passive"))
      (node (ref "R57") (pin "2") (pinfunction "2_2") (pintype "passive"))
    )
    (net (code "86") (name "Net-(IC10A--IN)") (class "Default")
      (node (ref "C69") (pin "2") (pinfunction "2_2") (pintype "passive"))
      (node (ref "IC10") (pin "2") (pinfunction "-IN_2") (pintype "input"))
      (node (ref "R54") (pin "2") (pinfunction "2_2") (pintype "passive"))
      (node (ref "R55") (pin "1") (pinfunction "1_1") (pintype "passive"))
    )
    (net (code "87") (name "Net-(IC10A-OUT)") (class "Default")
      (node (ref "C69") (pin "1") (pinfunction "1_1") (pintype "passive"))
      (node (ref "IC10") (pin "1") (pinfunction "OUT_1") (pintype "output"))
      (node (ref "IC13") (pin "14") (pinfunction "CTRL1_14") (pintype "input"))
      (node (ref "R55") (pin "2") (pinfunction "2_2") (pintype "passive"))
    )
    (net (code "88") (name "Net-(IC10B-+IN)") (class "Default")
      (node (ref "IC10") (pin "5") (pinfunction "+IN_5") (pintype "input"))
      (node (ref "R32") (pin "2") (pinfunction "2_2") (pintype "passive"))
      (node (ref "R33") (pin "2") (pinfunction "2_2") (pintype "passive"))
    )
    (net (code "89") (name "Net-(IC10B--IN)") (class "Default")
      (node (ref "C48") (pin "2") (pinfunction "2_2") (pintype "passive"))
      (node (ref "IC10") (pin "6") (pinfunction "-IN_6") (pintype "input"))
      (node (ref "R30") (pin "2") (pinfunction "2_2") (pintype "passive"))
      (node (ref "R31") (pin "1") (pinfunction "1_1") (pintype "passive"))
    )
    (net (code "90") (name "Net-(IC10B-OUT)") (class "Default")
      (node (ref "C48") (pin "1") (pinfunction "1_1") (pintype "passive"))
      (node (ref "IC10") (pin "7") (pinfunction "OUT_7") (pintype "output"))
      (node (ref "IC11") (pin "14") (pinfunction "CTRL1_14") (pintype "input"))
      (node (ref "R31") (pin "2") (pinfunction "2_2") (pintype "passive"))
    )
    (net (code "91") (name "Net-(IC11-BG)") (class "Default")
      (node (ref "IC11") (pin "1") (pinfunction "BG_1") (pintype "output"))
      (node (ref "Q3") (pin "1") (pinfunction "G_1") (pintype "passive"))
    )
    (net (code "92") (name "Net-(IC11-BOOST)") (class "Default")
      (node (ref "C54") (pin "1") (pinfunction "1_1") (pintype "passive"))
      (node (ref "D6") (pin "C") (pinfunction "C_C") (pintype "passive"))
      (node (ref "IC11") (pin "27") (pinfunction "BOOST_27") (pintype "passive"))
    )
    (net (code "93") (name "Net-(IC11-ISMON)") (class "Default")
      (node (ref "IC11") (pin "19") (pinfunction "ISMON_19") (pintype "output"))
      (node (ref "R38") (pin "2") (pinfunction "2_2") (pintype "passive"))
    )
    (net (code "94") (name "Net-(IC11-PWM)") (class "Default")
      (node (ref "IC11") (pin "22") (pinfunction "PWM_22") (pintype "input"))
      (node (ref "R43") (pin "2") (pinfunction "2_2") (pintype "passive"))
    )
    (net (code "95") (name "Net-(IC11-RT)") (class "Default")
      (node (ref "IC11") (pin "20") (pinfunction "RT_20") (pintype "input"))
      (node (ref "R42") (pin "2") (pinfunction "2_2") (pintype "passive"))
    )
    (net (code "96") (name "Net-(IC11-SENSE+)") (class "Default")
      (node (ref "C65") (pin "1") (pinfunction "1_1") (pintype "passive"))
      (node (ref "IC11") (pin "17") (pinfunction "SENSE+_17") (pintype "input"))
      (node (ref "R35") (pin "1") (pinfunction "1_1") (pintype "passive"))
    )
    (net (code "97") (name "Net-(IC11-SENSE-)") (class "Default")
      (node (ref "C65") (pin "2") (pinfunction "2_2") (pintype "passive"))
      (node (ref "IC11") (pin "16") (pinfunction "SENSE-_16") (pintype "input"))
      (node (ref "R36") (pin "1") (pinfunction "1_1") (pintype "passive"))
    )
    (net (code "98") (name "Net-(IC11-SS)") (class "Default")
      (node (ref "C66") (pin "2") (pinfunction "2_2") (pintype "passive"))
      (node (ref "IC11") (pin "15") (pinfunction "SS_15") (pintype "input"))
    )
    (net (code "99") (name "Net-(IC11-SW)") (class "Default")
      (node (ref "C54") (pin "2") (pinfunction "2_2") (pintype "passive"))
      (node (ref "C58") (pin "1") (pinfunction "1_1") (pintype "passive"))
      (node (ref "D7") (pin "C") (pinfunction "C_C") (pintype "passive"))
      (node (ref "IC11") (pin "26") (pinfunction "SW_26") (pintype "output"))
      (node (ref "L2") (pin "1") (pinfunction "1_1") (pintype "passive"))
      (node (ref "Q2") (pin "3") (pinfunction "S_3") (pintype "passive"))
      (node (ref "Q3") (pin "2") (pinfunction "D_2") (pintype "passive"))
    )
    (net (code "100") (name "Net-(IC11-TG)") (class "Default")
      (node (ref "IC11") (pin "25") (pinfunction "TG_25") (pintype "output"))
      (node (ref "Q2") (pin "1") (pinfunction "G_1") (pintype "passive"))
    )
    (net (code "101") (name "Net-(IC11-VC)") (class "Default")
      (node (ref "C67") (pin "2") (pinfunction "2_2") (pintype "passive"))
      (node (ref "IC11") (pin "18") (pinfunction "VC_18") (pintype "passive"))
    )
    (net (code "102") (name "Net-(IC11-VIN)") (class "Default")
      (node (ref "C49") (pin "1") (pinfunction "1_1") (pintype "passive"))
      (node (ref "D3") (pin "C") (pinfunction "C_C") (pintype "passive"))
      (node (ref "D5") (pin "C") (pinfunction "C_C") (pintype "passive"))
      (node (ref "IC11") (pin "3") (pinfunction "VIN_3") (pintype "passive"))
    )
    (net (code "103") (name "Net-(IC11-~{FAULT})") (class "Default")
      (node (ref "IC11") (pin "9") (pinfunction "~{FAULT}_9") (pintype "output"))
      (node (ref "R44") (pin "1") (pinfunction "1_1") (pintype "passive"))
    )
    (net (code "104") (name "Net-(IC12A-+IN)") (class "Default")
      (node (ref "IC12") (pin "3") (pinfunction "+IN_3") (pintype "input"))
      (node (ref "R74") (pin "1") (pinfunction "1_1") (pintype "passive"))
      (node (ref "R75") (pin "2") (pinfunction "2_2") (pintype "passive"))
    )
    (net (code "105") (name "Net-(IC12A--IN)") (class "Default")
      (node (ref "IC12") (pin "13") (pinfunction "-IN_13") (pintype "input"))
      (node (ref "IC12") (pin "14") (pinfunction "OUT_14") (pintype "output"))
      (node (ref "IC12") (pin "2") (pinfunction "-IN_2") (pintype "input"))
    )
    (net (code "106") (name "Net-(IC12B-+IN)") (class "Default")
      (node (ref "IC12") (pin "5") (pinfunction "+IN_5") (pintype "input"))
      (node (ref "R50") (pin "1") (pinfunction "1_1") (pintype "passive"))
      (node (ref "R51") (pin "2") (pinfunction "2_2") (pintype "passive"))
    )
    (net (code "107") (name "Net-(IC12B--IN)") (class "Default")
      (node (ref "IC12") (pin "6") (pinfunction "-IN_6") (pintype "input"))
      (node (ref "IC12") (pin "8") (pinfunction "OUT_8") (pintype "output"))
      (node (ref "IC12") (pin "9") (pinfunction "-IN_9") (pintype "input"))
    )
    (net (code "108") (name "Net-(IC13-BG)") (class "Default")
      (node (ref "IC13") (pin "1") (pinfunction "BG_1") (pintype "output"))
      (node (ref "Q8") (pin "1") (pinfunction "G_1") (pintype "passive"))
    )
    (net (code "109") (name "Net-(IC13-BOOST)") (class "Default")
      (node (ref "C74") (pin "1") (pinfunction "1_1") (pintype "passive"))
      (node (ref "D11") (pin "C") (pinfunction "C_C") (pintype "passive"))
      (node (ref "IC13") (pin "27") (pinfunction "BOOST_27") (pintype "passive"))
    )
    (net (code "110") (name "Net-(IC13-ISMON)") (class "Default")
      (node (ref "IC13") (pin "19") (pinfunction "ISMON_19") (pintype "output"))
      (node (ref "R62") (pin "2") (pinfunction "2_2") (pintype "passive"))
    )
    (net (code "111") (name "Net-(IC13-PWM)") (class "Default")
      (node (ref "IC13") (pin "22") (pinfunction "PWM_22") (pintype "input"))
      (node (ref "R67") (pin "2") (pinfunction "2_2") (pintype "passive"))
    )
    (net (code "112") (name "Net-(IC13-RT)") (class "Default")
      (node (ref "IC13") (pin "20") (pinfunction "RT_20") (pintype "input"))
      (node (ref "R66") (pin "2") (pinfunction "2_2") (pintype "passive"))
    )
    (net (code "113") (name "Net-(IC13-SENSE+)") (class "Default")
      (node (ref "C85") (pin "1") (pinfunction "1_1") (pintype "passive"))
      (node (ref "IC13") (pin "17") (pinfunction "SENSE+_17") (pintype "input"))
      (node (ref "R59") (pin "1") (pinfunction "1_1") (pintype "passive"))
    )
    (net (code "114") (name "Net-(IC13-SENSE-)") (class "Default")
      (node (ref "C85") (pin "2") (pinfunction "2_2") (pintype "passive"))
      (node (ref "IC13") (pin "16") (pinfunction "SENSE-_16") (pintype "input"))
      (node (ref "R60") (pin "1") (pinfunction "1_1") (pintype "passive"))
    )
    (net (code "115") (name "Net-(IC13-SS)") (class "Default")
      (node (ref "C86") (pin "2") (pinfunction "2_2") (pintype "passive"))
      (node (ref "IC13") (pin "15") (pinfunction "SS_15") (pintype "input"))
    )
    (net (code "116") (name "Net-(IC13-SW)") (class "Default")
      (node (ref "C74") (pin "2") (pinfunction "2_2") (pintype "passive"))
      (node (ref "C78") (pin "1") (pinfunction "1_1") (pintype "passive"))
      (node (ref "D12") (pin "C") (pinfunction "C_C") (pintype "passive"))
      (node (ref "IC13") (pin "26") (pinfunction "SW_26") (pintype "output"))
      (node (ref "L4") (pin "1") (pinfunction "1_1") (pintype "passive"))
      (node (ref "Q7") (pin "3") (pinfunction "S_3") (pintype "passive"))
      (node (ref "Q8") (pin "2") (pinfunction "D_2") (pintype "passive"))
    )
    (net (code "117") (name "Net-(IC13-TG)") (class "Default")
      (node (ref "IC13") (pin "25") (pinfunction "TG_25") (pintype "output"))
      (node (ref "Q7") (pin "1") (pinfunction "G_1") (pintype "passive"))
    )
    (net (code "118") (name "Net-(IC13-VC)") (class "Default")
      (node (ref "C87") (pin "2") (pinfunction "2_2") (pintype "passive"))
      (node (ref "IC13") (pin "18") (pinfunction "VC_18") (pintype "passive"))
    )
    (net (code "119") (name "Net-(IC13-VIN)") (class "Default")
      (node (ref "C70") (pin "1") (pinfunction "1_1") (pintype "passive"))
      (node (ref "D10") (pin "C") (pinfunction "C_C") (pintype "passive"))
      (node (ref "D8") (pin "C") (pinfunction "C_C") (pintype "passive"))
      (node (ref "IC13") (pin "3") (pinfunction "VIN_3") (pintype "passive"))
    )
    (net (code "120") (name "Net-(IC13-~{FAULT})") (class "Default")
      (node (ref "IC13") (pin "9") (pinfunction "~{FAULT}_9") (pintype "output"))
      (node (ref "R68") (pin "1") (pinfunction "1_1") (pintype "passive"))
    )
    (net (code "121") (name "Net-(L1A-1)") (class "Default")
      (node (ref "C1") (pin "2") (pinfunction "2_2") (pintype "passive"))
      (node (ref "L1") (pin "3") (pinfunction "1_3") (pintype "passive"))
      (node (ref "R1") (pin "2") (pinfunction "2_2") (pintype "passive"))
      (node (ref "X1") (pin "1") (pinfunction "1_1") (pintype "passive"))
    )
    (net (code "122") (name "Net-(L2-Pad2)") (class "Default")
      (node (ref "L2") (pin "2") (pinfunction "2_2") (pintype "passive"))
      (node (ref "R34") (pin "1") (pinfunction "1_1") (pintype "passive"))
    )
    (net (code "123") (name "Net-(L4-Pad2)") (class "Default")
      (node (ref "L4") (pin "2") (pinfunction "2_2") (pintype "passive"))
      (node (ref "R58") (pin "1") (pinfunction "1_1") (pintype "passive"))
    )
    (net (code "124") (name "Net-(LED1-AG)") (class "Default")
      (node (ref "LED1") (pin "GREEN") (pinfunction "AG_GREEN") (pintype "passive"))
      (node (ref "Q4") (pin "2") (pinfunction "S_2") (pintype "passive"))
    )
    (net (code "125") (name "Net-(LED1-AR)") (class "Default")
      (node (ref "LED1") (pin "RED") (pinfunction "AR_RED") (pintype "passive"))
      (node (ref "R49") (pin "1") (pinfunction "1_1") (pintype "passive"))
    )
    (net (code "126") (name "Net-(LED2-AG)") (class "Default")
      (node (ref "LED2") (pin "GREEN") (pinfunction "AG_GREEN") (pintype "passive"))
      (node (ref "Q9") (pin "2") (pinfunction "S_2") (pintype "passive"))
    )
    (net (code "127") (name "Net-(LED2-AR)") (class "Default")
      (node (ref "LED2") (pin "RED") (pinfunction "AR_RED") (pintype "passive"))
      (node (ref "R73") (pin "1") (pinfunction "1_1") (pintype "passive"))
    )
    (net (code "128") (name "Net-(Q1-D-Pad2)") (class "Default")
      (node (ref "Q1") (pin "2") (pinfunction "D_2") (pintype "passive"))
      (node (ref "Q1") (pin "4") (pinfunction "D_4") (pintype "passive"))
      (node (ref "R28") (pin "2") (pinfunction "2_2") (pintype "passive"))
    )
    (net (code "129") (name "Net-(Q1-G)") (class "Default")
      (node (ref "D4") (pin "C") (pinfunction "C_C") (pintype "passive"))
      (node (ref "Q1") (pin "1") (pinfunction "G_1") (pintype "passive"))
      (node (ref "R29") (pin "2") (pinfunction "2_2") (pintype "passive"))
      (node (ref "ZD2") (pin "C") (pinfunction "C_C") (pintype "passive"))
    )
    (net (code "130") (name "Net-(Q1-S)") (class "Default")
      (node (ref "D3") (pin "A") (pinfunction "A_A") (pintype "passive"))
      (node (ref "D4") (pin "A") (pinfunction "A_A") (pintype "passive"))
      (node (ref "Q1") (pin "3") (pinfunction "S_3") (pintype "passive"))
    )
    (net (code "131") (name "Net-(Q4-D)") (class "Default")
      (node (ref "Q4") (pin "3") (pinfunction "D_3") (pintype "passive"))
      (node (ref "Q5") (pin "3") (pinfunction "D_3") (pintype "passive"))
    )
    (net (code "132") (name "Net-(Q6-D-Pad2)") (class "Default")
      (node (ref "Q6") (pin "2") (pinfunction "D_2") (pintype "passive"))
      (node (ref "Q6") (pin "4") (pinfunction "D_4") (pintype "passive"))
      (node (ref "R52") (pin "2") (pinfunction "2_2") (pintype "passive"))
    )
    (net (code "133") (name "Net-(Q6-G)") (class "Default")
      (node (ref "D9") (pin "C") (pinfunction "C_C") (pintype "passive"))
      (node (ref "Q6") (pin "1") (pinfunction "G_1") (pintype "passive"))
      (node (ref "R53") (pin "2") (pinfunction "2_2") (pintype "passive"))
      (node (ref "ZD4") (pin "C") (pinfunction "C_C") (pintype "passive"))
    )
    (net (code "134") (name "Net-(Q6-S)") (class "Default")
      (node (ref "D8") (pin "A") (pinfunction "A_A") (pintype "passive"))
      (node (ref "D9") (pin "A") (pinfunction "A_A") (pintype "passive"))
      (node (ref "Q6") (pin "3") (pinfunction "S_3") (pintype "passive"))
    )
    (net (code "135") (name "Net-(Q10-D)") (class "Default")
      (node (ref "Q10") (pin "3") (pinfunction "D_3") (pintype "passive"))
      (node (ref "Q9") (pin "3") (pinfunction "D_3") (pintype "passive"))
    )
    (net (code "136") (name "Net-(R34-Pad1S)") (class "Default")
      (node (ref "R34") (pin "1S") (pinfunction "1S_1S") (pintype "passive"))
      (node (ref "R35") (pin "2") (pinfunction "2_2") (pintype "passive"))
    )
    (net (code "137") (name "Net-(R34-Pad2S)") (class "Default")
      (node (ref "R34") (pin "2S") (pinfunction "2S_2S") (pintype "passive"))
      (node (ref "R36") (pin "2") (pinfunction "2_2") (pintype "passive"))
    )
    (net (code "138") (name "Net-(R58-Pad1S)") (class "Default")
      (node (ref "R58") (pin "1S") (pinfunction "1S_1S") (pintype "passive"))
      (node (ref "R59") (pin "2") (pinfunction "2_2") (pintype "passive"))
    )
    (net (code "139") (name "Net-(R58-Pad2S)") (class "Default")
      (node (ref "R58") (pin "2S") (pinfunction "2S_2S") (pintype "passive"))
      (node (ref "R60") (pin "2") (pinfunction "2_2") (pintype "passive"))
    )
    (net (code "140") (name "Net-(X1B-1)") (class "Default")
      (node (ref "C1") (pin "1") (pinfunction "1_1") (pintype "passive"))
      (node (ref "L1") (pin "1") (pinfunction "1_1") (pintype "passive"))
      (node (ref "R1") (pin "1") (pinfunction "1_1") (pintype "passive"))
      (node (ref "X1") (pin "2") (pinfunction "1_2") (pintype "passive"))
    )
    (net (code "141") (name "Net-(X3A-S)") (class "Default")
      (node (ref "JP2") (pin "2") (pinfunction "2_2") (pintype "passive"))
      (node (ref "R19") (pin "2") (pinfunction "2_2") (pintype "passive"))
      (node (ref "X3") (pin "1") (pinfunction "S_1") (pintype "passive"))
    )
    (net (code "142") (name "OE#1") (class "Default")
      (node (ref "IC11") (pin "4") (pinfunction "EV/UVLO_4") (pintype "input"))
      (node (ref "OE#1") (pin "2") (pinfunction "2_2") (pintype "passive"))
      (node (ref "Q4") (pin "1") (pinfunction "G_1") (pintype "passive"))
    )
    (net (code "143") (name "OE#2") (class "Default")
      (node (ref "IC13") (pin "4") (pinfunction "EV/UVLO_4") (pintype "input"))
      (node (ref "OE#2") (pin "2") (pinfunction "2_2") (pintype "passive"))
      (node (ref "Q9") (pin "1") (pinfunction "G_1") (pintype "passive"))
    )
    (net (code "144") (name "OE_SYNC") (class "Default")
      (node (ref "IC8") (pin "36") (pinfunction "PF7_36") (pintype "bidirectional"))
      (node (ref "RN1") (pin "8") (pinfunction "2_8") (pintype "passive"))
    )
    (net (code "145") (name "PE") (class "Default")
      (node (ref "C2") (pin "2") (pinfunction "2_2") (pintype "passive"))
      (node (ref "C3") (pin "1") (pinfunction "1_1") (pintype "passive"))
      (node (ref "C56") (pin "1") (pinfunction "1_1") (pintype "passive"))
      (node (ref "C63") (pin "1") (pinfunction "1_1") (pintype "passive"))
      (node (ref "C76") (pin "1") (pinfunction "1_1") (pintype "passive"))
      (node (ref "C83") (pin "1") (pinfunction "1_1") (pintype "passive"))
      (node (ref "J1") (pin "1") (pinfunction "P$1_1") (pintype "bidirectional"))
      (node (ref "J1") (pin "2") (pinfunction "P$1_2") (pintype "bidirectional"))
    )
    (net (code "146") (name "PWRGOOD") (class "Default")
      (node (ref "IC2") (pin "6") (pinfunction "PWRGD_6") (pintype "output"))
      (node (ref "IC8") (pin "40") (pinfunction "PB4_40") (pintype "bidirectional"))
    )
    (net (code "147") (name "SCLK") (class "Default")
      (node (ref "IC8") (pin "29") (pinfunction "PA8_29") (pintype "bidirectional"))
      (node (ref "RN1") (pin "7") (pinfunction "2_7") (pintype "passive"))
    )
    (net (code "148") (name "SWCLK") (class "Default")
      (node (ref "IC8") (pin "37") (pinfunction "PA14_37") (pintype "bidirectional"))
      (node (ref "RN2") (pin "2") (pinfunction "1_2") (pintype "passive"))
    )
    (net (code "149") (name "SWDIO") (class "Default")
      (node (ref "IC8") (pin "34") (pinfunction "PA13_34") (pintype "bidirectional"))
      (node (ref "RN2") (pin "4") (pinfunction "1_4") (pintype "passive"))
    )
    (net (code "150") (name "SWO") (class "Default")
      (node (ref "IC8") (pin "39") (pinfunction "PB3_39") (pintype "bidirectional"))
      (node (ref "RN2") (pin "1") (pinfunction "1_1") (pintype "passive"))
    )
    (net (code "151") (name "TCK") (class "Default")
      (node (ref "IC7") (pin "5") (pinfunction "IO4_5") (pintype "bidirectional"))
      (node (ref "RN2") (pin "7") (pinfunction "2_7") (pintype "passive"))
      (node (ref "X3") (pin "2") (pinfunction "S_2") (pintype "passive"))
    )
    (net (code "152") (name "TEMP#1") (class "Default")
      (node (ref "C34") (pin "2") (pinfunction "2_2") (pintype "passive"))
      (node (ref "IC8") (pin "10") (pinfunction "PA0_10") (pintype "bidirectional"))
      (node (ref "NTC1") (pin "2") (pinfunction "P$2_2") (pintype "bidirectional"))
      (node (ref "R21") (pin "1") (pinfunction "1_1") (pintype "passive"))
    )
    (net (code "153") (name "TEMP#2") (class "Default")
      (node (ref "C35") (pin "2") (pinfunction "2_2") (pintype "passive"))
      (node (ref "IC8") (pin "14") (pinfunction "PA4_14") (pintype "bidirectional"))
      (node (ref "NTC2") (pin "2") (pinfunction "P$2_2") (pintype "bidirectional"))
      (node (ref "R22") (pin "1") (pinfunction "1_1") (pintype "passive"))
    )
    (net (code "154") (name "TMS") (class "Default")
      (node (ref "IC7") (pin "4") (pinfunction "IO3_4") (pintype "bidirectional"))
      (node (ref "RN2") (pin "5") (pinfunction "2_5") (pintype "passive"))
      (node (ref "X3") (pin "4") (pinfunction "S_4") (pintype "passive"))
    )
    (net (code "155") (name "UART_RX") (class "Default")
      (node (ref "IC3") (pin "12") (pinfunction "B3_12") (pintype "output"))
      (node (ref "IC8") (pin "13") (pinfunction "PA3_13") (pintype "bidirectional"))
    )
    (net (code "156") (name "UART_TX") (class "Default")
      (node (ref "IC3") (pin "11") (pinfunction "B4_11") (pintype "input"))
      (node (ref "IC8") (pin "12") (pinfunction "PA2_12") (pintype "bidirectional"))
    )
    (net (code "157") (name "U_MON#1") (class "Default")
      (node (ref "C41") (pin "2") (pinfunction "2_2") (pintype "passive"))
      (node (ref "IC8") (pin "18") (pinfunction "PB0_18") (pintype "bidirectional"))
      (node (ref "R24") (pin "1") (pinfunction "1_1") (pintype "passive"))
    )
    (net (code "158") (name "U_MON#2") (class "Default")
      (node (ref "C43") (pin "2") (pinfunction "2_2") (pintype "passive"))
      (node (ref "IC8") (pin "20") (pinfunction "PB2_20") (pintype "bidirectional"))
      (node (ref "R26") (pin "1") (pinfunction "1_1") (pintype "passive"))
    )
    (net (code "159") (name "U_MON1") (class "Default")
      (node (ref "R24") (pin "2") (pinfunction "2_2") (pintype "passive"))
      (node (ref "R40") (pin "1") (pinfunction "1_1") (pintype "passive"))
      (node (ref "R47") (pin "2") (pinfunction "2_2") (pintype "passive"))
    )
    (net (code "160") (name "U_MON2") (class "Default")
      (node (ref "R26") (pin "2") (pinfunction "2_2") (pintype "passive"))
      (node (ref "R64") (pin "1") (pinfunction "1_1") (pintype "passive"))
      (node (ref "R71") (pin "2") (pinfunction "2_2") (pintype "passive"))
    )
    (net (code "161") (name "U_SET#1") (class "Default")
      (node (ref "R48") (pin "1") (pinfunction "1_1") (pintype "passive"))
      (node (ref "U_SET1") (pin "1") (pinfunction "1_1") (pintype "passive"))
    )
    (net (code "162") (name "U_SET#2") (class "Default")
      (node (ref "R72") (pin "1") (pinfunction "1_1") (pintype "passive"))
      (node (ref "U_SET2") (pin "1") (pinfunction "1_1") (pintype "passive"))
    )
    (net (code "163") (name "U_SET_OUT#1") (class "Default")
      (node (ref "IC8") (pin "16") (pinfunction "PA6_16") (pintype "bidirectional"))
      (node (ref "U_SET1") (pin "2") (pinfunction "2_2") (pintype "passive"))
    )
    (net (code "164") (name "U_SET_OUT#2") (class "Default")
      (node (ref "IC8") (pin "15") (pinfunction "PA5_15") (pintype "bidirectional"))
      (node (ref "U_SET2") (pin "2") (pinfunction "2_2") (pintype "passive"))
    )
    (net (code "165") (name "V+") (class "Default")
      (node (ref "C17") (pin "1") (pinfunction "1_1") (pintype "passive"))
      (node (ref "C20") (pin "2") (pinfunction "2_2") (pintype "passive"))
      (node (ref "C7") (pin "1") (pinfunction "1_1") (pintype "passive"))
      (node (ref "IC1") (pin "1") (pinfunction "VDD1_1") (pintype "passive"))
      (node (ref "IC3") (pin "1") (pinfunction "VDD1_1") (pintype "passive"))
      (node (ref "IC3") (pin "7") (pinfunction "EN1_7") (pintype "input"))
      (node (ref "IC4") (pin "8") (pinfunction "VCC_8") (pintype "power_in"))
      (node (ref "R11") (pin "1") (pinfunction "1_1") (pintype "passive"))
      (node (ref "R12") (pin "1") (pinfunction "1_1") (pintype "passive"))
      (node (ref "R13") (pin "1") (pinfunction "1_1") (pintype "passive"))
      (node (ref "X2") (pin "1") (pinfunction "1_1") (pintype "passive"))
    )
    (net (code "166") (name "VDDA") (class "Default")
      (node (ref "C37") (pin "2") (pinfunction "2_2") (pintype "passive"))
      (node (ref "C38") (pin "2") (pinfunction "2_2") (pintype "passive"))
      (node (ref "FB1") (pin "P$2") (pinfunction "2_P$2") (pintype "passive"))
      (node (ref "IC8") (pin "24") (pinfunction "VDDSD_24") (pintype "passive"))
      (node (ref "IC8") (pin "9") (pinfunction "VDDA/VREF+_9") (pintype "passive"))
    )
    (net (code "167") (name "VOUT1+") (class "Default")
      (node (ref "C59") (pin "1") (pinfunction "1_1") (pintype "passive"))
      (node (ref "C60") (pin "1") (pinfunction "1_1") (pintype "passive"))
      (node (ref "C62") (pin "+") (pinfunction "+_+") (pintype "passive"))
      (node (ref "L3") (pin "1") (pinfunction "1_1") (pintype "passive"))
      (node (ref "R34") (pin "2") (pinfunction "2_2") (pintype "passive"))
      (node (ref "R39") (pin "2") (pinfunction "2_2") (pintype "passive"))
      (node (ref "R40") (pin "2") (pinfunction "2_2") (pintype "passive"))
      (node (ref "ZD2") (pin "A") (pinfunction "A_A") (pintype "passive"))
    )
    (net (code "168") (name "VOUT2+") (class "Default")
      (node (ref "C79") (pin "1") (pinfunction "1_1") (pintype "passive"))
      (node (ref "C80") (pin "1") (pinfunction "1_1") (pintype "passive"))
      (node (ref "C82") (pin "+") (pinfunction "+_+") (pintype "passive"))
      (node (ref "L5") (pin "1") (pinfunction "1_1") (pintype "passive"))
      (node (ref "R58") (pin "2") (pinfunction "2_2") (pintype "passive"))
      (node (ref "R63") (pin "2") (pinfunction "2_2") (pintype "passive"))
      (node (ref "R64") (pin "2") (pinfunction "2_2") (pintype "passive"))
      (node (ref "ZD4") (pin "A") (pinfunction "A_A") (pintype "passive"))
    )
    (net (code "169") (name "VOUT_LC1+") (class "Default")
      (node (ref "C56") (pin "2") (pinfunction "2_2") (pintype "passive"))
      (node (ref "C57") (pin "1") (pinfunction "1_1") (pintype "passive"))
      (node (ref "C61") (pin "1") (pinfunction "+_1") (pintype "passive"))
      (node (ref "CH1") (pin "TIP") (pinfunction "TIP_TIP") (pintype "bidirectional"))
      (node (ref "J2") (pin "1") (pinfunction "1_1") (pintype "passive"))
      (node (ref "J2") (pin "1.1") (pinfunction "1_1.1") (pintype "passive"))
      (node (ref "L3") (pin "2") (pinfunction "2_2") (pintype "passive"))
      (node (ref "R41") (pin "1") (pinfunction "1_1") (pintype "passive"))
      (node (ref "ZD3") (pin "C") (pinfunction "C_C") (pintype "passive"))
    )
    (net (code "170") (name "VOUT_LC2+") (class "Default")
      (node (ref "C76") (pin "2") (pinfunction "2_2") (pintype "passive"))
      (node (ref "C77") (pin "1") (pinfunction "1_1") (pintype "passive"))
      (node (ref "C81") (pin "1") (pinfunction "+_1") (pintype "passive"))
      (node (ref "CH2") (pin "TIP") (pinfunction "TIP_TIP") (pintype "bidirectional"))
      (node (ref "J4") (pin "1") (pinfunction "1_1") (pintype "passive"))
      (node (ref "J4") (pin "1.1") (pinfunction "1_1.1") (pintype "passive"))
      (node (ref "L5") (pin "2") (pinfunction "2_2") (pintype "passive"))
      (node (ref "R65") (pin "1") (pinfunction "1_1") (pintype "passive"))
      (node (ref "ZD5") (pin "C") (pinfunction "C_C") (pintype "passive"))
    )
    (net (code "171") (name "VREF1") (class "Default")
      (node (ref "C53") (pin "1") (pinfunction "1_1") (pintype "passive"))
      (node (ref "IC11") (pin "10") (pinfunction "FBIN_10") (pintype "input"))
      (node (ref "IC11") (pin "13") (pinfunction "CTRL2_13") (pintype "input"))
      (node (ref "IC11") (pin "5") (pinfunction "VREF_5") (pintype "output"))
      (node (ref "R50") (pin "2") (pinfunction "2_2") (pintype "passive"))
    )
    (net (code "172") (name "VREF2") (class "Default")
      (node (ref "C73") (pin "1") (pinfunction "1_1") (pintype "passive"))
      (node (ref "IC13") (pin "10") (pinfunction "FBIN_10") (pintype "input"))
      (node (ref "IC13") (pin "13") (pinfunction "CTRL2_13") (pintype "input"))
      (node (ref "IC13") (pin "5") (pinfunction "VREF_5") (pintype "output"))
      (node (ref "R74") (pin "2") (pinfunction "2_2") (pintype "passive"))
    )
    (net (code "173") (name "unconnected-(IC8-PA15-Pad38)") (class "Default")
      (node (ref "IC8") (pin "38") (pinfunction "PA15_38") (pintype "bidirectional"))
    )
    (net (code "174") (name "unconnected-(IC8-PB7-Pad43)") (class "Default")
      (node (ref "IC8") (pin "43") (pinfunction "PB7_43") (pintype "bidirectional"))
    )
    (net (code "175") (name "unconnected-(IC8-PB14-Pad26)") (class "Default")
      (node (ref "IC8") (pin "26") (pinfunction "PB14_26") (pintype "bidirectional"))
    )
    (net (code "176") (name "unconnected-(IC8-PB15-Pad27)") (class "Default")
      (node (ref "IC8") (pin "27") (pinfunction "PB15_27") (pintype "bidirectional"))
    )
    (net (code "177") (name "unconnected-(IC8-PD8-Pad28)") (class "Default")
      (node (ref "IC8") (pin "28") (pinfunction "PD8_28") (pintype "bidirectional"))
    )
    (net (code "178") (name "unconnected-(IC8-PE9-Pad22)") (class "Default")
      (node (ref "IC8") (pin "22") (pinfunction "PE9_22") (pintype "bidirectional"))
    )
    (net (code "179") (name "unconnected-(IC8-PF6-Pad35)") (class "Default")
      (node (ref "IC8") (pin "35") (pinfunction "PF6_35") (pintype "bidirectional"))
    )
    (net (code "180") (name "unconnected-(IC8-VBAT-Pad1)") (class "Default")
      (node (ref "IC8") (pin "1") (pinfunction "VBAT_1") (pintype "passive"))
    )
    (net (code "181") (name "unconnected-(IC11-IVINMON-Pad8)") (class "Default")
      (node (ref "IC11") (pin "8") (pinfunction "IVINMON_8") (pintype "output"))
    )
    (net (code "182") (name "unconnected-(IC11-PWMOUT-Pad24)") (class "Default")
      (node (ref "IC11") (pin "24") (pinfunction "PWMOUT_24") (pintype "output"))
    )
    (net (code "183") (name "unconnected-(IC13-IVINMON-Pad8)") (class "Default")
      (node (ref "IC13") (pin "8") (pinfunction "IVINMON_8") (pintype "output"))
    )
    (net (code "184") (name "unconnected-(IC13-PWMOUT-Pad24)") (class "Default")
      (node (ref "IC13") (pin "24") (pinfunction "PWMOUT_24") (pintype "output"))
    )
    (net (code "185") (name "~{RESET}") (class "Default")
      (node (ref "IC1") (pin "15") (pinfunction "B1_15") (pintype "output"))
      (node (ref "JP3") (pin "1") (pinfunction "1_1") (pintype "passive"))
    )
  )
)
